# Glowdeck_beta_proto.net
KiCad netlist of a schematic drawn in EAGLE
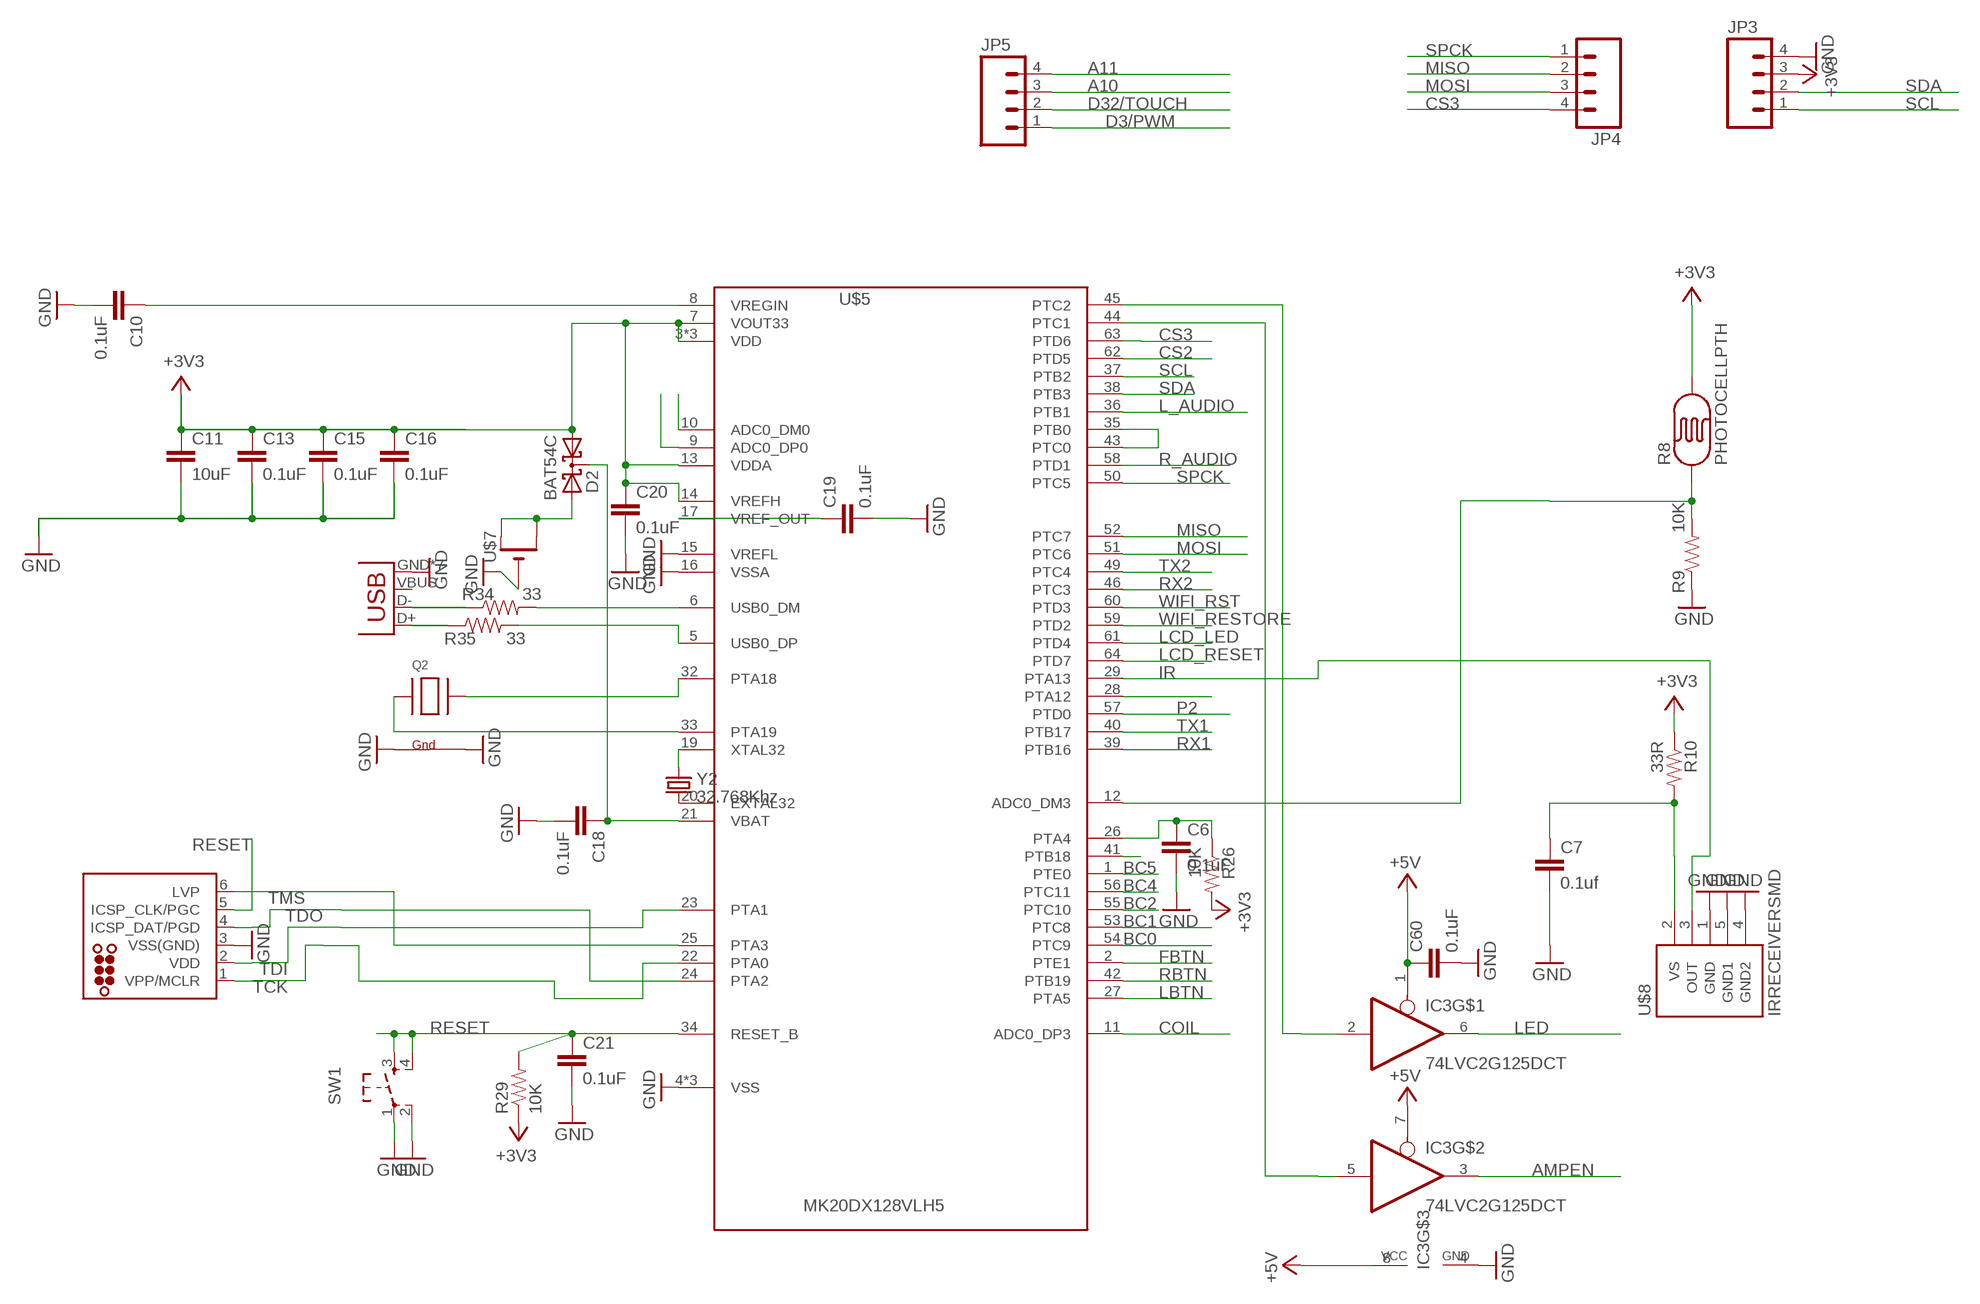
[diagram p0: schematic, sheet 1]
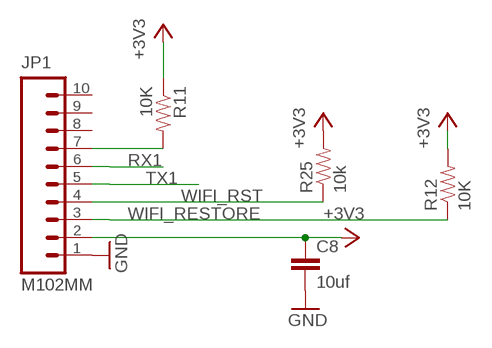
[diagram p1: schematic, sheet 2]
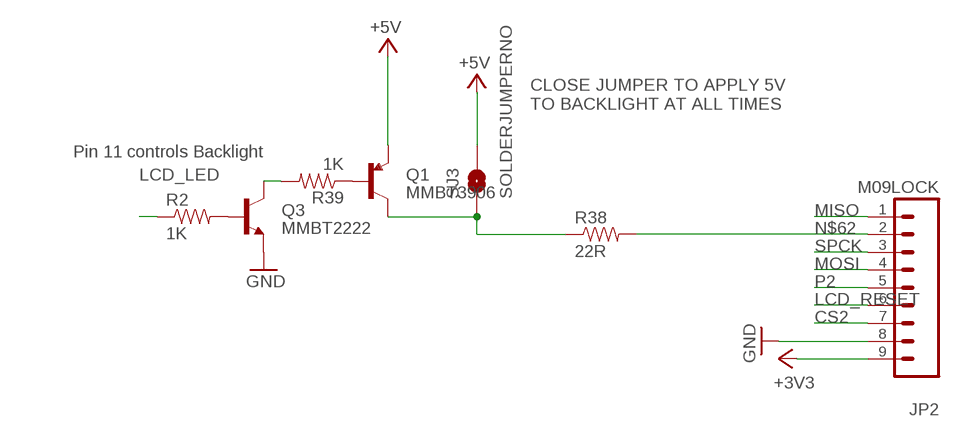
[diagram p2: schematic, sheet 3]
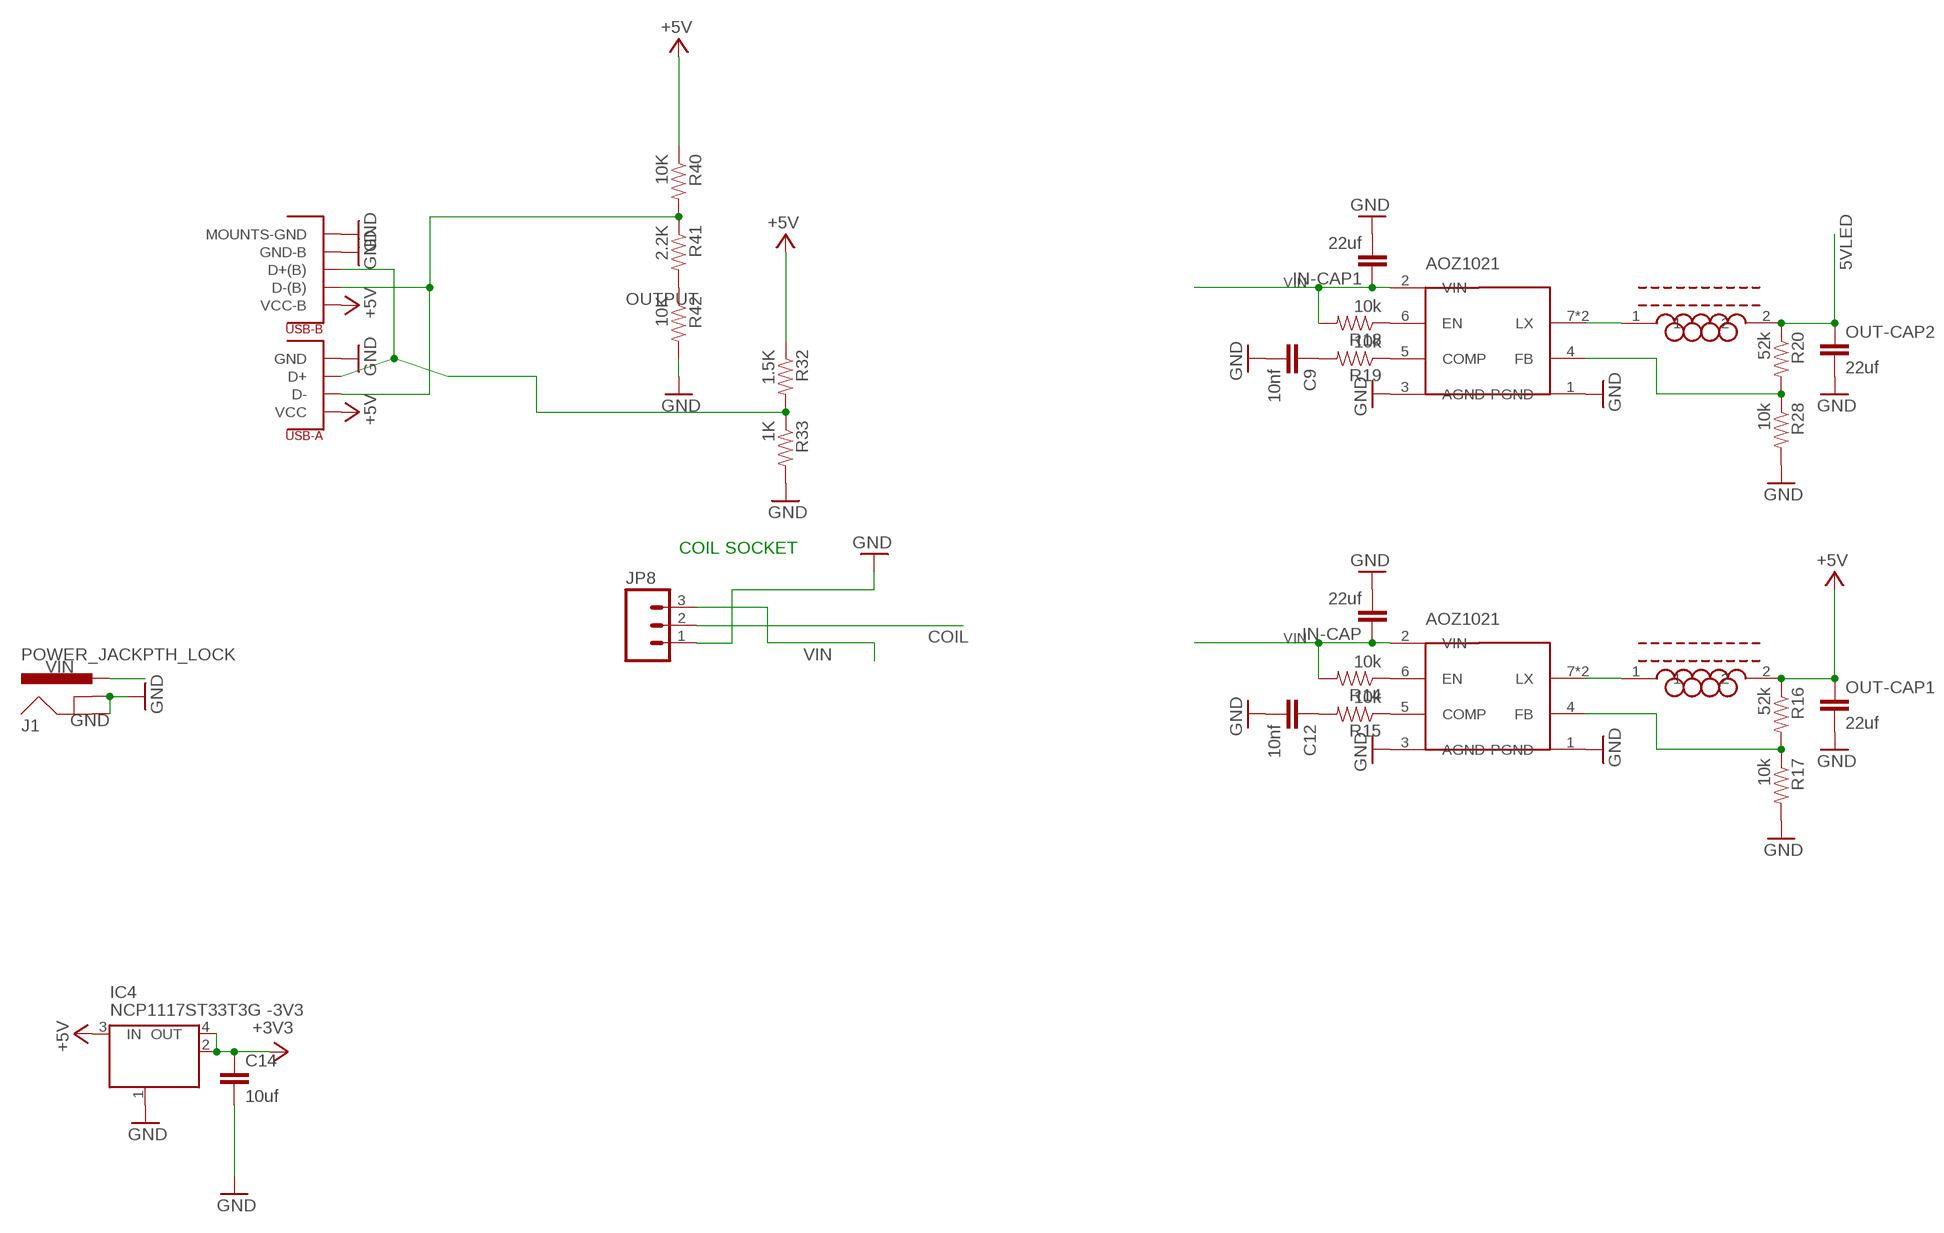
[diagram p3: schematic, sheet 4]
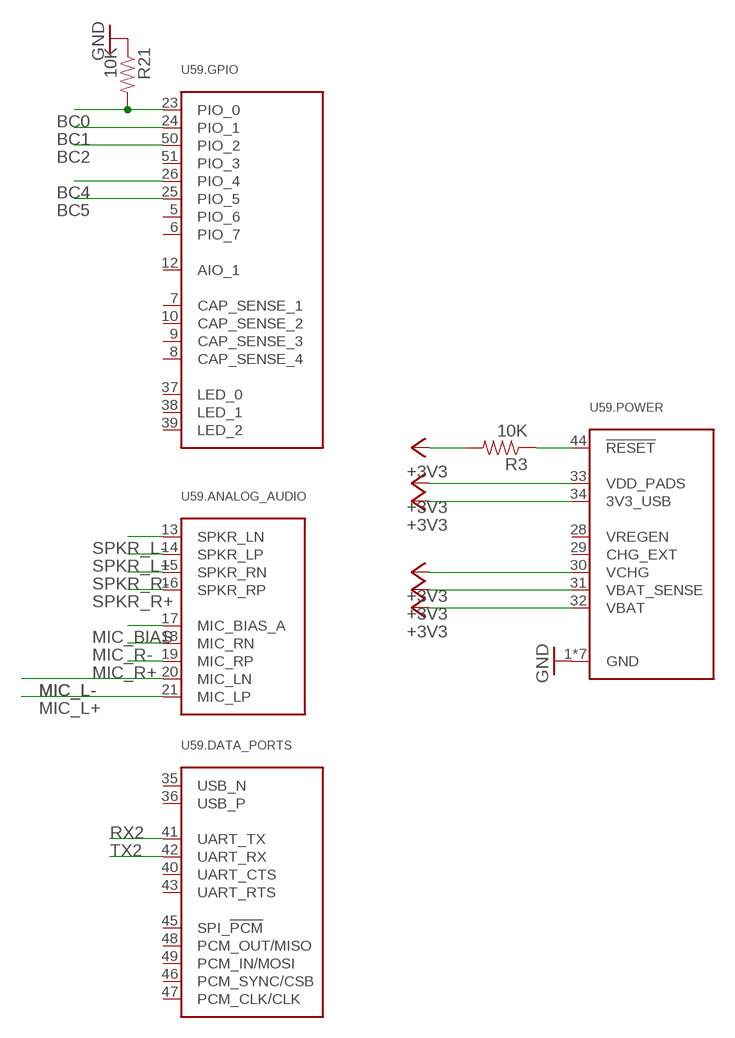
[diagram p4: schematic, sheet 5]
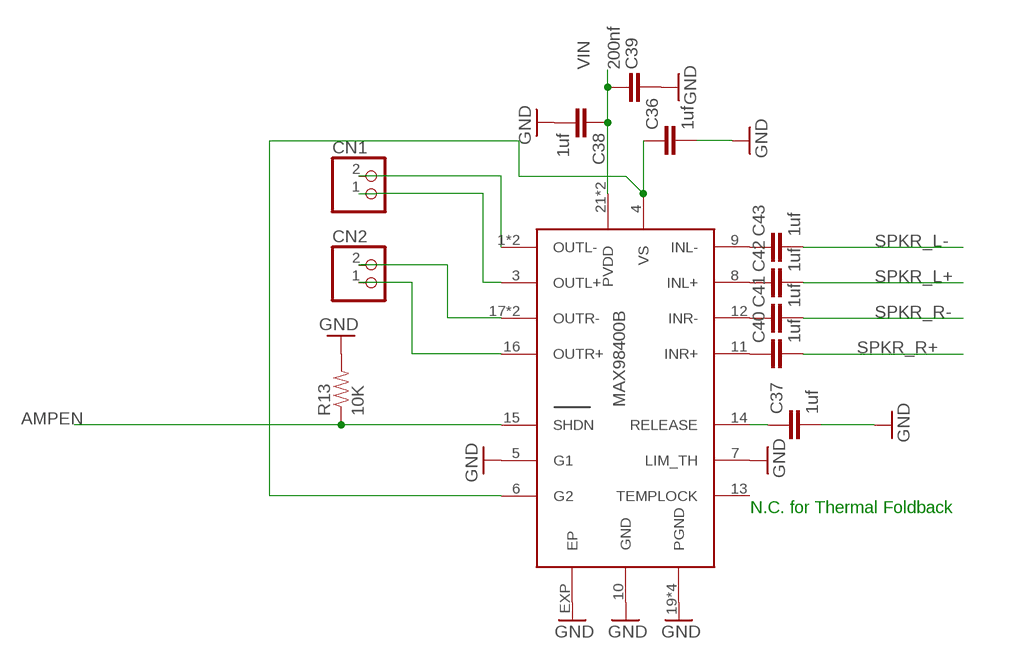
[diagram p5: schematic, sheet 6]
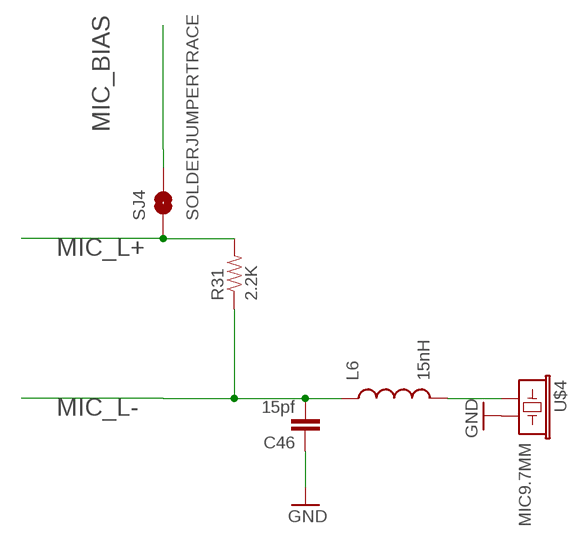
[diagram p6: schematic, sheet 7]
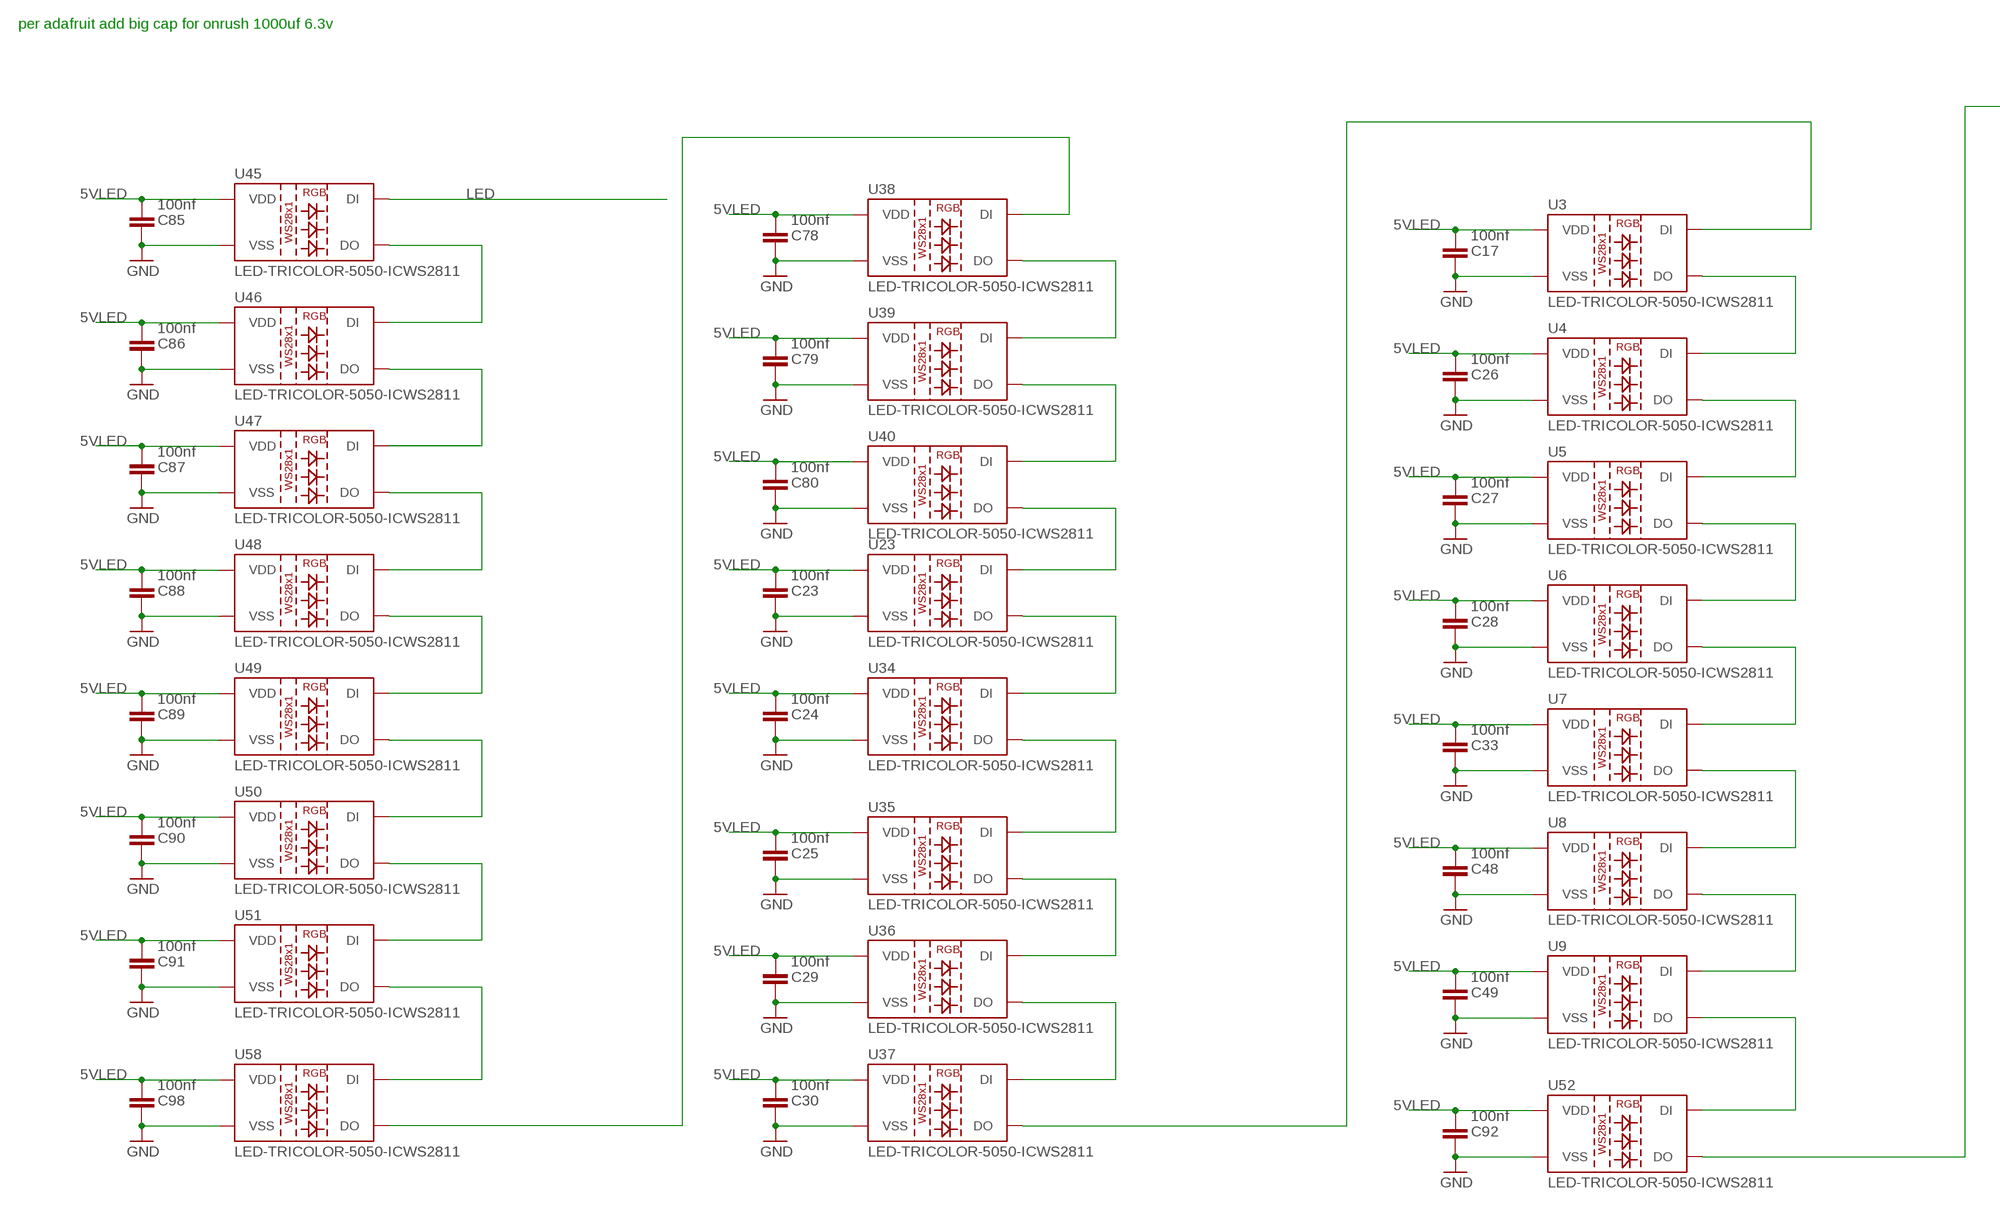
[diagram p7: schematic, sheet 8, part 1 of 2]
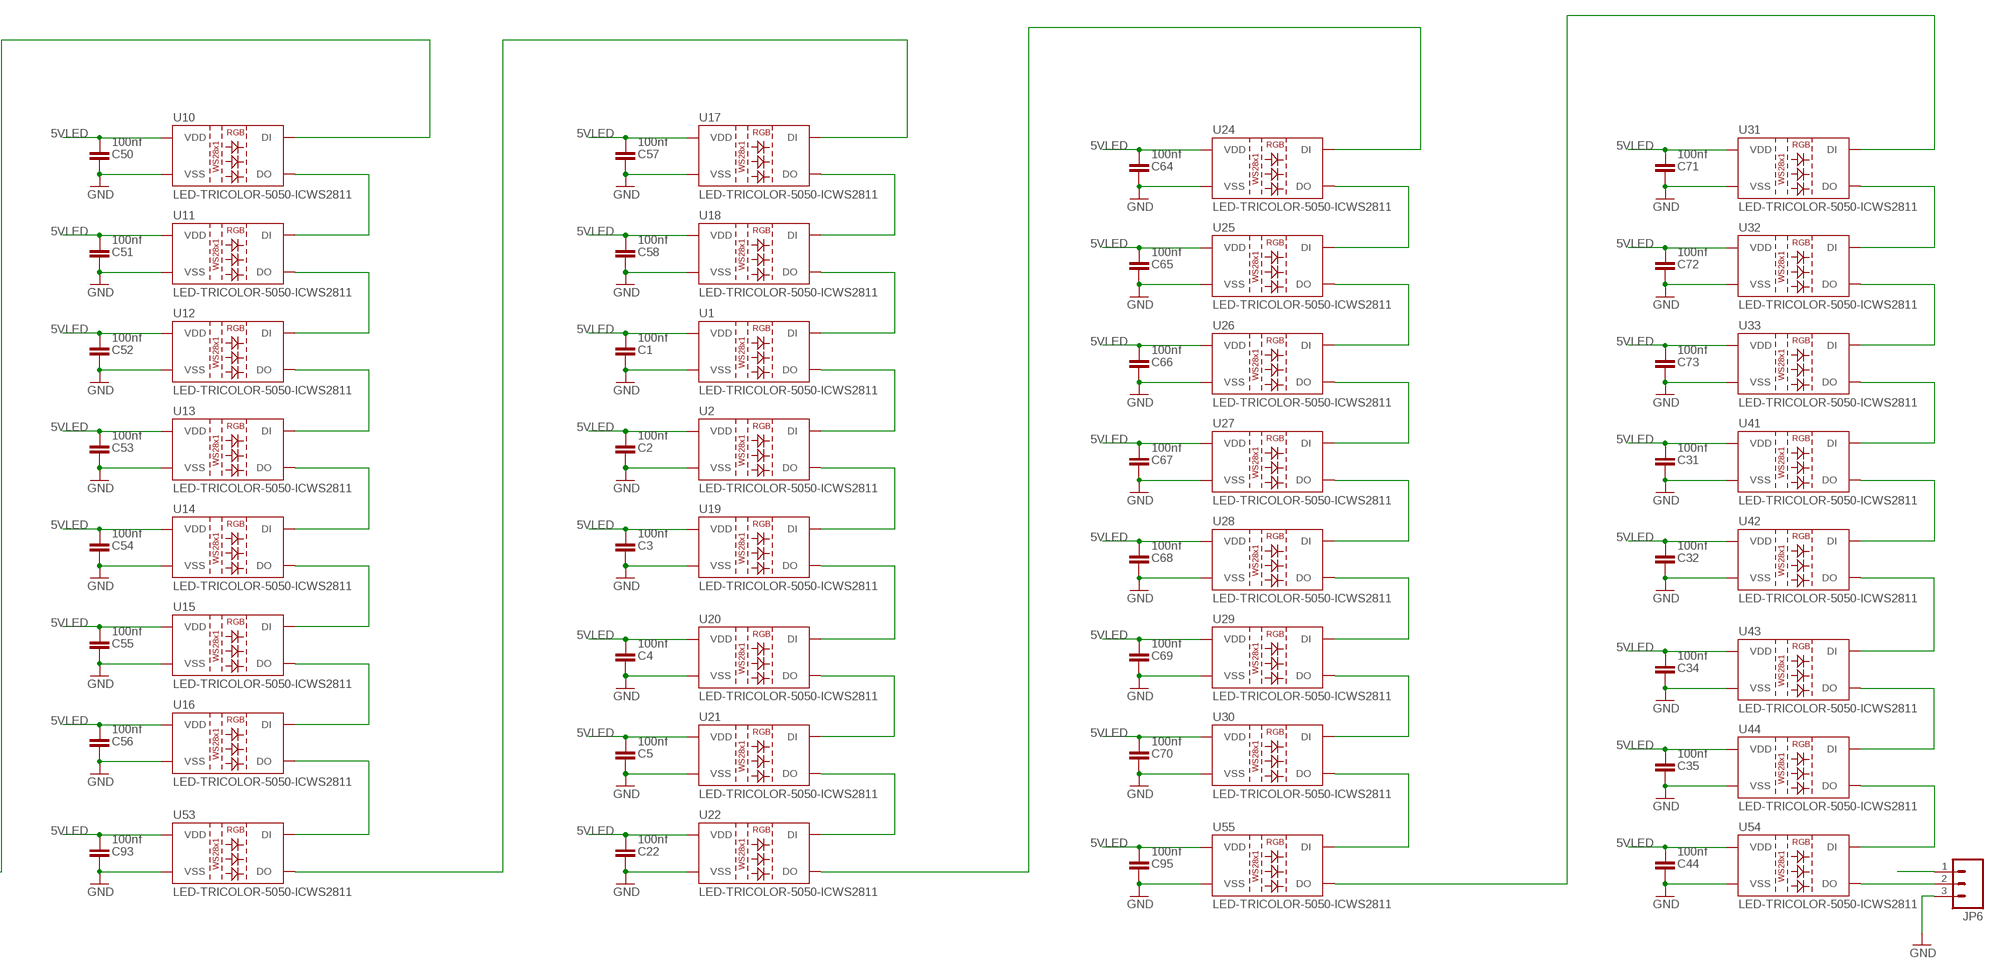
[diagram p8: schematic, sheet 8, part 2 of 2]
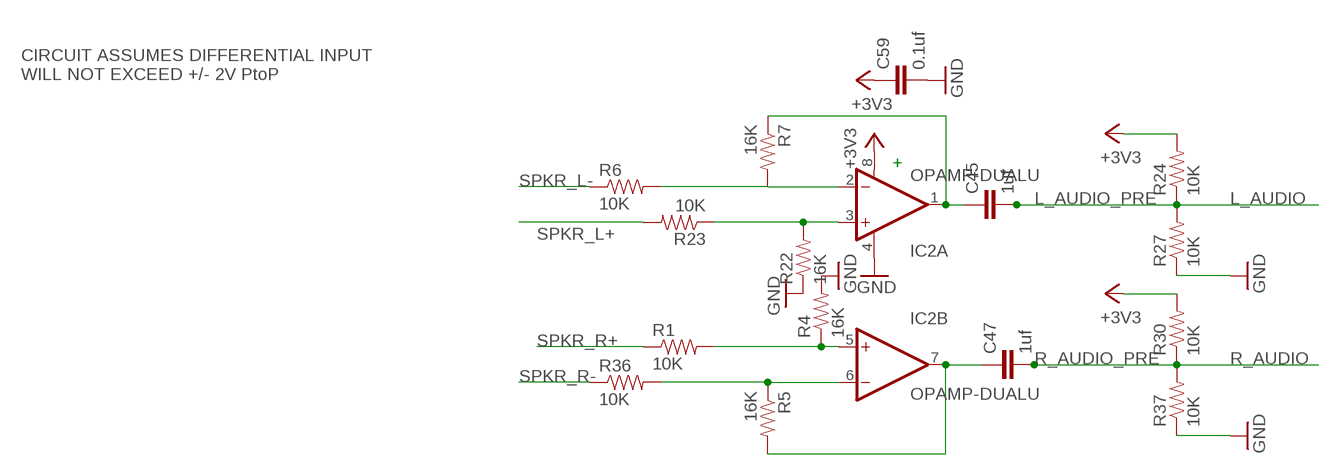
[diagram p9: schematic, sheet 9]
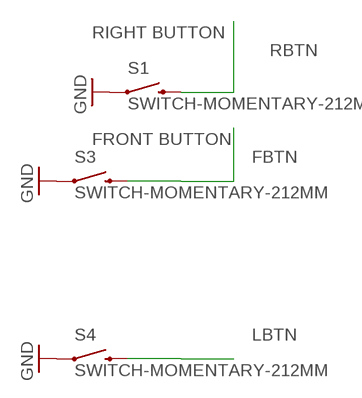
[diagram p10: schematic, sheet 10]
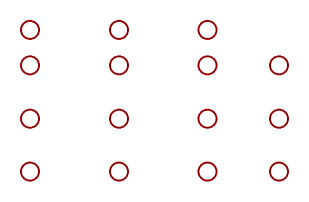
[diagram p11: schematic, sheet 11]

(export (version "E")
  (design (tool "Eeschema 10.0.6"))
  (components
    (comp (ref "C8")
      (value "10uf")
      (footprint "eagle-import:0805")
      (libsource (lib "eagle-import") (part "CAP0805"))
    )
    (comp (ref "JP1")
      (value "M102MM")
      (footprint "eagle-import:1X10-2MM")
      (libsource (lib "eagle-import") (part "M102MM"))
    )
    (comp (ref "R11")
      (value "10K")
      (footprint "eagle-import:0603-RES")
      (libsource (lib "eagle-import") (part "RESISTOR0603-RES"))
    )
    (comp (ref "R12")
      (value "10K")
      (footprint "eagle-import:0603-RES")
      (libsource (lib "eagle-import") (part "RESISTOR0603-RES"))
    )
    (comp (ref "R25")
      (value "10k")
      (footprint "eagle-import:0603-RES")
      (libsource (lib "eagle-import") (part "RESISTOR0603-RES"))
    )
    (comp (ref "C36")
      (value "1uf")
      (footprint "eagle-import:0805")
      (libsource (lib "eagle-import") (part "CAP0805"))
    )
    (comp (ref "C37")
      (value "1uf")
      (footprint "eagle-import:0805")
      (libsource (lib "eagle-import") (part "CAP0805"))
    )
    (comp (ref "C38")
      (value "1uf")
      (footprint "eagle-import:0805")
      (libsource (lib "eagle-import") (part "CAP0805"))
    )
    (comp (ref "C39")
      (value "200nf")
      (footprint "eagle-import:0603-CAP")
      (libsource (lib "eagle-import") (part "CAP0603-CAP"))
    )
    (comp (ref "C40")
      (value "1uf")
      (footprint "eagle-import:0805")
      (libsource (lib "eagle-import") (part "CAP0805"))
    )
    (comp (ref "C41")
      (value "1uf")
      (footprint "eagle-import:0805")
      (libsource (lib "eagle-import") (part "CAP0805"))
    )
    (comp (ref "C42")
      (value "1uf")
      (footprint "eagle-import:0805")
      (libsource (lib "eagle-import") (part "CAP0805"))
    )
    (comp (ref "C43")
      (value "1uf")
      (footprint "eagle-import:0805")
      (libsource (lib "eagle-import") (part "CAP0805"))
    )
    (comp (ref "CN1")
      (value "JST_2PIN-THM")
      (footprint "eagle-import:JST-PH-2-THM")
      (libsource (lib "eagle-import") (part "JST_2PIN-THM"))
    )
    (comp (ref "CN2")
      (value "JST_2PIN-THM")
      (footprint "eagle-import:JST-PH-2-THM")
      (libsource (lib "eagle-import") (part "JST_2PIN-THM"))
    )
    (comp (ref "R13")
      (value "10K")
      (footprint "eagle-import:0603-RES")
      (libsource (lib "eagle-import") (part "RESISTOR0603-RES"))
    )
    (comp (ref "U$3")
      (value "MAX98400B")
      (footprint "eagle-import:TQFN24-EP")
      (libsource (lib "eagle-import") (part "MAX98400B"))
    )
    (comp (ref "JP2")
      (value "M09LOCK")
      (footprint "eagle-import:1X09_LOCK")
      (libsource (lib "eagle-import") (part "M09LOCK"))
    )
    (comp (ref "Q1")
      (value "MMBT3906")
      (footprint "eagle-import:SOT23-3")
      (libsource (lib "eagle-import") (part "TRANSISTOR_PNPSMD"))
    )
    (comp (ref "Q3")
      (value "MMBT2222")
      (footprint "eagle-import:SOT23-3")
      (libsource (lib "eagle-import") (part "TRANSISTOR_NPNSOT23-3"))
    )
    (comp (ref "R2")
      (value "1K")
      (footprint "eagle-import:0603-RES")
      (libsource (lib "eagle-import") (part "SparkFun-Passives_RESISTOR0603-RES"))
    )
    (comp (ref "R38")
      (value "22R")
      (footprint "eagle-import:1206")
      (libsource (lib "eagle-import") (part "SparkFun-Resistors_RESISTOR1206"))
    )
    (comp (ref "R39")
      (value "1K")
      (footprint "eagle-import:0603-RES")
      (libsource (lib "eagle-import") (part "SparkFun-Passives_RESISTOR0603-RES"))
    )
    (comp (ref "SJ3")
      (value "SOLDERJUMPERNO")
      (footprint "eagle-import:SJ_2S-NO")
      (libsource (lib "eagle-import") (part "SOLDERJUMPERNO"))
    )
    (comp (ref "C6")
      (value "0.1uF")
      (footprint "eagle-import:0603-CAP")
      (libsource (lib "eagle-import") (part "SparkFun-Passives_CAP0603-CAP"))
    )
    (comp (ref "C7")
      (value "0.1uf")
      (footprint "eagle-import:0603-CAP")
      (libsource (lib "eagle-import") (part "SparkFun-Passives_CAP0603-CAP"))
    )
    (comp (ref "C10")
      (value "0.1uF")
      (footprint "eagle-import:0603-CAP")
      (libsource (lib "eagle-import") (part "SparkFun-Passives_CAP0603-CAP"))
    )
    (comp (ref "C11")
      (value "10uF")
      (footprint "eagle-import:0805")
      (libsource (lib "eagle-import") (part "SparkFun-Passives_CAP0805"))
    )
    (comp (ref "C13")
      (value "0.1uF")
      (footprint "eagle-import:0603-CAP")
      (libsource (lib "eagle-import") (part "SparkFun-Passives_CAP0603-CAP"))
    )
    (comp (ref "C15")
      (value "0.1uF")
      (footprint "eagle-import:0603-CAP")
      (libsource (lib "eagle-import") (part "SparkFun-Passives_CAP0603-CAP"))
    )
    (comp (ref "C16")
      (value "0.1uF")
      (footprint "eagle-import:0603-CAP")
      (libsource (lib "eagle-import") (part "SparkFun-Passives_CAP0603-CAP"))
    )
    (comp (ref "C18")
      (value "0.1uF")
      (footprint "eagle-import:0603-CAP")
      (libsource (lib "eagle-import") (part "SparkFun-Passives_CAP0603-CAP"))
    )
    (comp (ref "C19")
      (value "0.1uF")
      (footprint "eagle-import:0603-CAP")
      (libsource (lib "eagle-import") (part "SparkFun-Passives_CAP0603-CAP"))
    )
    (comp (ref "C20")
      (value "0.1uF")
      (footprint "eagle-import:0603-CAP")
      (libsource (lib "eagle-import") (part "SparkFun-Passives_CAP0603-CAP"))
    )
    (comp (ref "C21")
      (value "0.1uF")
      (footprint "eagle-import:0603-CAP")
      (libsource (lib "eagle-import") (part "SparkFun-Passives_CAP0603-CAP"))
    )
    (comp (ref "C60")
      (value "0.1uF")
      (footprint "eagle-import:0603-CAP")
      (libsource (lib "eagle-import") (part "SparkFun-Passives_CAP0603-CAP"))
    )
    (comp (ref "D2")
      (value "BAT54C")
      (footprint "eagle-import:SOT23")
      (libsource (lib "eagle-import") (part "BAT54C"))
    )
    (comp (ref "IC3")
      (value "74LVC2G125DCT")
      (footprint "eagle-import:SSOP08")
      (libsource (lib "eagle-import") (part "742G125DCTLVC"))
    )
    (comp (ref "J2")
      (value "TC2030-MCP-NL")
      (footprint "eagle-import:TC2030-MCP-NL")
      (libsource (lib "eagle-import") (part "TC2030-MCP-NL"))
    )
    (comp (ref "JP3")
      (value "M04LOCK")
      (footprint "eagle-import:1X04_LOCK")
      (libsource (lib "eagle-import") (part "M04LOCK"))
    )
    (comp (ref "JP4")
      (value "M04LOCK")
      (footprint "eagle-import:1X04_LOCK")
      (libsource (lib "eagle-import") (part "M04LOCK"))
    )
    (comp (ref "JP5")
      (value "M04LOCK")
      (footprint "eagle-import:1X04_LOCK")
      (libsource (lib "eagle-import") (part "M04LOCK"))
    )
    (comp (ref "Q2")
      (value "XTAL-4-3225")
      (footprint "eagle-import:NX3225")
      (libsource (lib "eagle-import") (part "XTAL-4-3225"))
    )
    (comp (ref "R8")
      (value "PHOTOCELLPTH")
      (footprint "eagle-import:PHOTOCELL")
      (libsource (lib "eagle-import") (part "PHOTOCELLPTH"))
    )
    (comp (ref "R9")
      (value "10K")
      (footprint "eagle-import:0603-RES")
      (libsource (lib "eagle-import") (part "SparkFun-Resistors_RESISTOR0603-RES"))
    )
    (comp (ref "R10")
      (value "33R")
      (footprint "eagle-import:0603-RES")
      (libsource (lib "eagle-import") (part "SparkFun-Resistors_RESISTOR0603-RES"))
    )
    (comp (ref "R26")
      (value "10K")
      (footprint "eagle-import:0603-RES")
      (libsource (lib "eagle-import") (part "SparkFun-Resistors_RESISTOR0603-RES"))
    )
    (comp (ref "R29")
      (value "10K")
      (footprint "eagle-import:0603-RES")
      (libsource (lib "eagle-import") (part "SparkFun-Resistors_RESISTOR0603-RES"))
    )
    (comp (ref "R34")
      (value "33")
      (footprint "eagle-import:0603-RES")
      (libsource (lib "eagle-import") (part "SparkFun-Resistors_RESISTOR0603-RES"))
    )
    (comp (ref "R35")
      (value "33")
      (footprint "eagle-import:0603-RES")
      (libsource (lib "eagle-import") (part "SparkFun-Resistors_RESISTOR0603-RES"))
    )
    (comp (ref "SW1")
      (value "SW_TACT_4P")
      (footprint "eagle-import:SW_TACT_SMALL")
      (libsource (lib "eagle-import") (part "SW_TACT_4P"))
    )
    (comp (ref "U$5")
      (value "MK20DX128VLH5")
      (footprint "eagle-import:MK20DX128VLH5")
      (libsource (lib "eagle-import") (part "MK20DX128VLH5"))
    )
    (comp (ref "U$7")
      (value "CR1220THM")
      (footprint "eagle-import:CR1220-THM")
      (libsource (lib "eagle-import") (part "CR1220THM"))
    )
    (comp (ref "U$8")
      (value "IRRECEIVERSMD")
      (footprint "eagle-import:TSOP8523")
      (libsource (lib "eagle-import") (part "IRRECEIVERSMD"))
    )
    (comp (ref "X3")
      (value "USB-MICROB")
      (footprint "eagle-import:USB-MICROB")
      (libsource (lib "eagle-import") (part "USB-MICROB"))
    )
    (comp (ref "Y2")
      (value "32.768Khz")
      (footprint "eagle-import:RESONATOR_EPSON_FC_145")
      (libsource (lib "eagle-import") (part "RESONATOR_EPSON_FC_145"))
    )
    (comp (ref "AOZ1015AI")
      (value "AOZ1021")
      (footprint "eagle-import:SO-08")
      (libsource (lib "eagle-import") (part "AOZ1021"))
    )
    (comp (ref "AOZ1015AI1")
      (value "AOZ1021")
      (footprint "eagle-import:SO-08")
      (libsource (lib "eagle-import") (part "AOZ1021"))
    )
    (comp (ref "C9")
      (value "10nf")
      (footprint "eagle-import:0603-CAP")
      (libsource (lib "eagle-import") (part "CAP0603-CAP"))
    )
    (comp (ref "C12")
      (value "10nf")
      (footprint "eagle-import:0603-CAP")
      (libsource (lib "eagle-import") (part "CAP0603-CAP"))
    )
    (comp (ref "C14")
      (value "10uf")
      (footprint "eagle-import:0805")
      (libsource (lib "eagle-import") (part "CAP0805"))
    )
    (comp (ref "IC4")
      (value "NCP1117ST33T3G -3V3")
      (footprint "eagle-import:SOT223")
      (libsource (lib "eagle-import") (part "MC33269ST-3.3T3"))
    )
    (comp (ref "IN-CAP")
      (value "22uf")
      (footprint "eagle-import:1210")
      (libsource (lib "eagle-import") (part "CAP1210"))
    )
    (comp (ref "IN-CAP1")
      (value "22uf")
      (footprint "eagle-import:1210")
      (libsource (lib "eagle-import") (part "CAP1210"))
    )
    (comp (ref "J1")
      (value "POWER_JACKPTH_LOCK")
      (footprint "eagle-import:POWER_JACK_PTH_LOCK")
      (libsource (lib "eagle-import") (part "POWER_JACKPTH_LOCK"))
    )
    (comp (ref "JP8")
      (value "M03JST-PTH")
      (footprint "eagle-import:JST-3-PTH")
      (libsource (lib "eagle-import") (part "M03JST-PTH"))
    )
    (comp (ref "OUT-CAP1")
      (value "22uf")
      (footprint "eagle-import:1210")
      (libsource (lib "eagle-import") (part "CAP1210"))
    )
    (comp (ref "OUT-CAP2")
      (value "22uf")
      (footprint "eagle-import:1210")
      (libsource (lib "eagle-import") (part "CAP1210"))
    )
    (comp (ref "R14")
      (value "10k")
      (footprint "eagle-import:0603-RES")
      (libsource (lib "eagle-import") (part "RESISTOR0603-RES"))
    )
    (comp (ref "R15")
      (value "10k")
      (footprint "eagle-import:0603-RES")
      (libsource (lib "eagle-import") (part "RESISTOR0603-RES"))
    )
    (comp (ref "R16")
      (value "52k")
      (footprint "eagle-import:0603-RES")
      (libsource (lib "eagle-import") (part "RESISTOR0603-RES"))
    )
    (comp (ref "R17")
      (value "10k")
      (footprint "eagle-import:0603-RES")
      (libsource (lib "eagle-import") (part "RESISTOR0603-RES"))
    )
    (comp (ref "R18")
      (value "10k")
      (footprint "eagle-import:0603-RES")
      (libsource (lib "eagle-import") (part "RESISTOR0603-RES"))
    )
    (comp (ref "R19")
      (value "10k")
      (footprint "eagle-import:0603-RES")
      (libsource (lib "eagle-import") (part "RESISTOR0603-RES"))
    )
    (comp (ref "R20")
      (value "52k")
      (footprint "eagle-import:0603-RES")
      (libsource (lib "eagle-import") (part "RESISTOR0603-RES"))
    )
    (comp (ref "R28")
      (value "10k")
      (footprint "eagle-import:0603-RES")
      (libsource (lib "eagle-import") (part "RESISTOR0603-RES"))
    )
    (comp (ref "R32")
      (value "1.5K")
      (footprint "eagle-import:0603-RES")
      (libsource (lib "eagle-import") (part "SparkFun-Passives_RESISTOR0603-RES"))
    )
    (comp (ref "R33")
      (value "1K")
      (footprint "eagle-import:0603-RES")
      (libsource (lib "eagle-import") (part "SparkFun-Passives_RESISTOR0603-RES"))
    )
    (comp (ref "R40")
      (value "10K")
      (footprint "eagle-import:0603-RES")
      (libsource (lib "eagle-import") (part "SparkFun-Passives_RESISTOR0603-RES"))
    )
    (comp (ref "R41")
      (value "2.2K")
      (footprint "eagle-import:0603-RES")
      (libsource (lib "eagle-import") (part "SparkFun-Passives_RESISTOR0603-RES"))
    )
    (comp (ref "R42")
      (value "10K")
      (footprint "eagle-import:0603-RES")
      (libsource (lib "eagle-import") (part "SparkFun-Passives_RESISTOR0603-RES"))
    )
    (comp (ref "U$1")
      (value "SRP7030F")
      (footprint "eagle-import:SRP7030")
      (libsource (lib "eagle-import") (part "SRP7030F"))
    )
    (comp (ref "U$2")
      (value "SRP7030F")
      (footprint "eagle-import:SRP7030")
      (libsource (lib "eagle-import") (part "SRP7030F"))
    )
    (comp (ref "U$6")
      (value "DUAL-PORT-USB-REC")
      (footprint "eagle-import:DUAL-PORT-USB")
      (libsource (lib "eagle-import") (part "DUAL-PORT-USB-REC"))
    )
    (comp (ref "R3")
      (value "10K")
      (footprint "eagle-import:0603-RES")
      (libsource (lib "eagle-import") (part "RESISTOR0603-RES"))
    )
    (comp (ref "R21")
      (value "10K")
      (footprint "eagle-import:0603-RES")
      (libsource (lib "eagle-import") (part "RESISTOR0603-RES"))
    )
    (comp (ref "U59")
      (value "BC127EXTRA_PASTE")
      (footprint "eagle-import:BC127_XTRA_PASTE")
      (libsource (lib "eagle-import") (part "BC127EXTRA_PASTE"))
    )
    (comp (ref "C46")
      (value "15pf")
      (footprint "eagle-import:0805")
      (libsource (lib "eagle-import") (part "CAP0805"))
    )
    (comp (ref "L6")
      (value "15nH")
      (footprint "eagle-import:0603")
      (libsource (lib "eagle-import") (part "INDUCTOR0603"))
    )
    (comp (ref "R31")
      (value "2.2K")
      (footprint "eagle-import:0603-RES")
      (libsource (lib "eagle-import") (part "RESISTOR0603-RES"))
    )
    (comp (ref "SJ4")
      (value "SOLDERJUMPERTRACE")
      (footprint "eagle-import:SJ_2S-TRACE")
      (libsource (lib "eagle-import") (part "SOLDERJUMPERTRACE"))
    )
    (comp (ref "U$4")
      (value "MIC9.7MM")
      (footprint "eagle-import:MIC-9.7MM")
      (libsource (lib "eagle-import") (part "MIC9.7MM"))
    )
    (comp (ref "STANDOFF1")
      (value "STAND-OFF")
      (footprint "eagle-import:STAND-OFF")
      (libsource (lib "eagle-import") (part "STAND-OFF"))
    )
    (comp (ref "STANDOFF2")
      (value "STAND-OFF")
      (footprint "eagle-import:STAND-OFF")
      (libsource (lib "eagle-import") (part "STAND-OFF"))
    )
    (comp (ref "STANDOFF3")
      (value "STAND-OFF")
      (footprint "eagle-import:STAND-OFF")
      (libsource (lib "eagle-import") (part "STAND-OFF"))
    )
    (comp (ref "STANDOFF4")
      (value "STAND-OFF")
      (footprint "eagle-import:STAND-OFF")
      (libsource (lib "eagle-import") (part "STAND-OFF"))
    )
    (comp (ref "STANDOFF5")
      (value "STAND-OFF")
      (footprint "eagle-import:STAND-OFF")
      (libsource (lib "eagle-import") (part "STAND-OFF"))
    )
    (comp (ref "STANDOFF6")
      (value "STAND-OFF")
      (footprint "eagle-import:STAND-OFF")
      (libsource (lib "eagle-import") (part "STAND-OFF"))
    )
    (comp (ref "STANDOFF7")
      (value "STAND-OFF")
      (footprint "eagle-import:STAND-OFF")
      (libsource (lib "eagle-import") (part "STAND-OFF"))
    )
    (comp (ref "STANDOFF8")
      (value "STAND-OFF")
      (footprint "eagle-import:STAND-OFF")
      (libsource (lib "eagle-import") (part "STAND-OFF"))
    )
    (comp (ref "STANDOFF9")
      (value "STAND-OFF")
      (footprint "eagle-import:STAND-OFF")
      (libsource (lib "eagle-import") (part "STAND-OFF"))
    )
    (comp (ref "STANDOFF10")
      (value "STAND-OFF")
      (footprint "eagle-import:STAND-OFF")
      (libsource (lib "eagle-import") (part "STAND-OFF"))
    )
    (comp (ref "STANDOFF11")
      (value "STAND-OFF")
      (footprint "eagle-import:STAND-OFF")
      (libsource (lib "eagle-import") (part "STAND-OFF"))
    )
    (comp (ref "STANDOFF12")
      (value "STAND-OFF")
      (footprint "eagle-import:STAND-OFF")
      (libsource (lib "eagle-import") (part "STAND-OFF"))
    )
    (comp (ref "STANDOFF13")
      (value "STAND-OFF")
      (footprint "eagle-import:STAND-OFF")
      (libsource (lib "eagle-import") (part "STAND-OFF"))
    )
    (comp (ref "STANDOFF14")
      (value "STAND-OFF")
      (footprint "eagle-import:STAND-OFF")
      (libsource (lib "eagle-import") (part "STAND-OFF"))
    )
    (comp (ref "STANDOFF15")
      (value "STAND-OFF")
      (footprint "eagle-import:STAND-OFF")
      (libsource (lib "eagle-import") (part "STAND-OFF"))
    )
    (comp (ref "S1")
      (value "SWITCH-MOMENTARY-212MM")
      (footprint "eagle-import:TACTILE-PTH-12MM")
      (libsource (lib "eagle-import") (part "SWITCH-MOMENTARY-212MM"))
    )
    (comp (ref "S3")
      (value "SWITCH-MOMENTARY-212MM")
      (footprint "eagle-import:TACTILE-PTH-12MM")
      (libsource (lib "eagle-import") (part "SWITCH-MOMENTARY-212MM"))
    )
    (comp (ref "S4")
      (value "SWITCH-MOMENTARY-212MM")
      (footprint "eagle-import:TACTILE-PTH-12MM")
      (libsource (lib "eagle-import") (part "SWITCH-MOMENTARY-212MM"))
    )
    (comp (ref "C45")
      (value "1uf")
      (footprint "eagle-import:0805")
      (libsource (lib "eagle-import") (part "SparkFun-Passives_CAP0805"))
    )
    (comp (ref "C47")
      (value "1uf")
      (footprint "eagle-import:0805")
      (libsource (lib "eagle-import") (part "SparkFun-Passives_CAP0805"))
    )
    (comp (ref "C59")
      (value "0.1uf")
      (footprint "eagle-import:0603-CAP")
      (libsource (lib "eagle-import") (part "SparkFun-Passives_CAP0603-CAP"))
    )
    (comp (ref "IC2")
      (value "OPAMP-DUALU")
      (footprint "eagle-import:SO08")
      (libsource (lib "eagle-import") (part "OPAMP-DUALU"))
    )
    (comp (ref "R1")
      (value "10K")
      (footprint "eagle-import:0603-RES")
      (libsource (lib "eagle-import") (part "RESISTOR0603-RES"))
    )
    (comp (ref "R4")
      (value "16K")
      (footprint "eagle-import:0603-RES")
      (libsource (lib "eagle-import") (part "RESISTOR0603-RES"))
    )
    (comp (ref "R5")
      (value "16K")
      (footprint "eagle-import:0603-RES")
      (libsource (lib "eagle-import") (part "RESISTOR0603-RES"))
    )
    (comp (ref "R6")
      (value "10K")
      (footprint "eagle-import:0603-RES")
      (libsource (lib "eagle-import") (part "RESISTOR0603-RES"))
    )
    (comp (ref "R7")
      (value "16K")
      (footprint "eagle-import:0603-RES")
      (libsource (lib "eagle-import") (part "RESISTOR0603-RES"))
    )
    (comp (ref "R22")
      (value "16K")
      (footprint "eagle-import:0603-RES")
      (libsource (lib "eagle-import") (part "RESISTOR0603-RES"))
    )
    (comp (ref "R23")
      (value "10K")
      (footprint "eagle-import:0603-RES")
      (libsource (lib "eagle-import") (part "RESISTOR0603-RES"))
    )
    (comp (ref "R24")
      (value "10K")
      (footprint "eagle-import:0603-RES")
      (libsource (lib "eagle-import") (part "RESISTOR0603-RES"))
    )
    (comp (ref "R27")
      (value "10K")
      (footprint "eagle-import:0603-RES")
      (libsource (lib "eagle-import") (part "RESISTOR0603-RES"))
    )
    (comp (ref "R30")
      (value "10K")
      (footprint "eagle-import:0603-RES")
      (libsource (lib "eagle-import") (part "RESISTOR0603-RES"))
    )
    (comp (ref "R36")
      (value "10K")
      (footprint "eagle-import:0603-RES")
      (libsource (lib "eagle-import") (part "RESISTOR0603-RES"))
    )
    (comp (ref "R37")
      (value "10K")
      (footprint "eagle-import:0603-RES")
      (libsource (lib "eagle-import") (part "RESISTOR0603-RES"))
    )
    (comp (ref "C1")
      (value "100nf")
      (footprint "eagle-import:0603-CAP")
      (libsource (lib "eagle-import") (part "CAP0603-CAP"))
    )
    (comp (ref "C2")
      (value "100nf")
      (footprint "eagle-import:0603-CAP")
      (libsource (lib "eagle-import") (part "CAP0603-CAP"))
    )
    (comp (ref "C3")
      (value "100nf")
      (footprint "eagle-import:0603-CAP")
      (libsource (lib "eagle-import") (part "CAP0603-CAP"))
    )
    (comp (ref "C4")
      (value "100nf")
      (footprint "eagle-import:0603-CAP")
      (libsource (lib "eagle-import") (part "CAP0603-CAP"))
    )
    (comp (ref "C5")
      (value "100nf")
      (footprint "eagle-import:0603-CAP")
      (libsource (lib "eagle-import") (part "CAP0603-CAP"))
    )
    (comp (ref "C17")
      (value "100nf")
      (footprint "eagle-import:0603-CAP")
      (libsource (lib "eagle-import") (part "CAP0603-CAP"))
    )
    (comp (ref "C22")
      (value "100nf")
      (footprint "eagle-import:0603-CAP")
      (libsource (lib "eagle-import") (part "CAP0603-CAP"))
    )
    (comp (ref "C23")
      (value "100nf")
      (footprint "eagle-import:0603-CAP")
      (libsource (lib "eagle-import") (part "CAP0603-CAP"))
    )
    (comp (ref "C24")
      (value "100nf")
      (footprint "eagle-import:0603-CAP")
      (libsource (lib "eagle-import") (part "CAP0603-CAP"))
    )
    (comp (ref "C25")
      (value "100nf")
      (footprint "eagle-import:0603-CAP")
      (libsource (lib "eagle-import") (part "CAP0603-CAP"))
    )
    (comp (ref "C26")
      (value "100nf")
      (footprint "eagle-import:0603-CAP")
      (libsource (lib "eagle-import") (part "CAP0603-CAP"))
    )
    (comp (ref "C27")
      (value "100nf")
      (footprint "eagle-import:0603-CAP")
      (libsource (lib "eagle-import") (part "CAP0603-CAP"))
    )
    (comp (ref "C28")
      (value "100nf")
      (footprint "eagle-import:0603-CAP")
      (libsource (lib "eagle-import") (part "CAP0603-CAP"))
    )
    (comp (ref "C29")
      (value "100nf")
      (footprint "eagle-import:0603-CAP")
      (libsource (lib "eagle-import") (part "CAP0603-CAP"))
    )
    (comp (ref "C30")
      (value "100nf")
      (footprint "eagle-import:0603-CAP")
      (libsource (lib "eagle-import") (part "CAP0603-CAP"))
    )
    (comp (ref "C31")
      (value "100nf")
      (footprint "eagle-import:0603-CAP")
      (libsource (lib "eagle-import") (part "CAP0603-CAP"))
    )
    (comp (ref "C32")
      (value "100nf")
      (footprint "eagle-import:0603-CAP")
      (libsource (lib "eagle-import") (part "CAP0603-CAP"))
    )
    (comp (ref "C33")
      (value "100nf")
      (footprint "eagle-import:0603-CAP")
      (libsource (lib "eagle-import") (part "CAP0603-CAP"))
    )
    (comp (ref "C34")
      (value "100nf")
      (footprint "eagle-import:0603-CAP")
      (libsource (lib "eagle-import") (part "CAP0603-CAP"))
    )
    (comp (ref "C35")
      (value "100nf")
      (footprint "eagle-import:0603-CAP")
      (libsource (lib "eagle-import") (part "CAP0603-CAP"))
    )
    (comp (ref "C44")
      (value "100nf")
      (footprint "eagle-import:0603-CAP")
      (libsource (lib "eagle-import") (part "CAP0603-CAP"))
    )
    (comp (ref "C48")
      (value "100nf")
      (footprint "eagle-import:0603-CAP")
      (libsource (lib "eagle-import") (part "CAP0603-CAP"))
    )
    (comp (ref "C49")
      (value "100nf")
      (footprint "eagle-import:0603-CAP")
      (libsource (lib "eagle-import") (part "CAP0603-CAP"))
    )
    (comp (ref "C50")
      (value "100nf")
      (footprint "eagle-import:0603-CAP")
      (libsource (lib "eagle-import") (part "CAP0603-CAP"))
    )
    (comp (ref "C51")
      (value "100nf")
      (footprint "eagle-import:0603-CAP")
      (libsource (lib "eagle-import") (part "CAP0603-CAP"))
    )
    (comp (ref "C52")
      (value "100nf")
      (footprint "eagle-import:0603-CAP")
      (libsource (lib "eagle-import") (part "CAP0603-CAP"))
    )
    (comp (ref "C53")
      (value "100nf")
      (footprint "eagle-import:0603-CAP")
      (libsource (lib "eagle-import") (part "CAP0603-CAP"))
    )
    (comp (ref "C54")
      (value "100nf")
      (footprint "eagle-import:0603-CAP")
      (libsource (lib "eagle-import") (part "CAP0603-CAP"))
    )
    (comp (ref "C55")
      (value "100nf")
      (footprint "eagle-import:0603-CAP")
      (libsource (lib "eagle-import") (part "CAP0603-CAP"))
    )
    (comp (ref "C56")
      (value "100nf")
      (footprint "eagle-import:0603-CAP")
      (libsource (lib "eagle-import") (part "CAP0603-CAP"))
    )
    (comp (ref "C57")
      (value "100nf")
      (footprint "eagle-import:0603-CAP")
      (libsource (lib "eagle-import") (part "CAP0603-CAP"))
    )
    (comp (ref "C58")
      (value "100nf")
      (footprint "eagle-import:0603-CAP")
      (libsource (lib "eagle-import") (part "CAP0603-CAP"))
    )
    (comp (ref "C64")
      (value "100nf")
      (footprint "eagle-import:0603-CAP")
      (libsource (lib "eagle-import") (part "CAP0603-CAP"))
    )
    (comp (ref "C65")
      (value "100nf")
      (footprint "eagle-import:0603-CAP")
      (libsource (lib "eagle-import") (part "CAP0603-CAP"))
    )
    (comp (ref "C66")
      (value "100nf")
      (footprint "eagle-import:0603-CAP")
      (libsource (lib "eagle-import") (part "CAP0603-CAP"))
    )
    (comp (ref "C67")
      (value "100nf")
      (footprint "eagle-import:0603-CAP")
      (libsource (lib "eagle-import") (part "CAP0603-CAP"))
    )
    (comp (ref "C68")
      (value "100nf")
      (footprint "eagle-import:0603-CAP")
      (libsource (lib "eagle-import") (part "CAP0603-CAP"))
    )
    (comp (ref "C69")
      (value "100nf")
      (footprint "eagle-import:0603-CAP")
      (libsource (lib "eagle-import") (part "CAP0603-CAP"))
    )
    (comp (ref "C70")
      (value "100nf")
      (footprint "eagle-import:0603-CAP")
      (libsource (lib "eagle-import") (part "CAP0603-CAP"))
    )
    (comp (ref "C71")
      (value "100nf")
      (footprint "eagle-import:0603-CAP")
      (libsource (lib "eagle-import") (part "CAP0603-CAP"))
    )
    (comp (ref "C72")
      (value "100nf")
      (footprint "eagle-import:0603-CAP")
      (libsource (lib "eagle-import") (part "CAP0603-CAP"))
    )
    (comp (ref "C73")
      (value "100nf")
      (footprint "eagle-import:0603-CAP")
      (libsource (lib "eagle-import") (part "CAP0603-CAP"))
    )
    (comp (ref "C78")
      (value "100nf")
      (footprint "eagle-import:0603-CAP")
      (libsource (lib "eagle-import") (part "CAP0603-CAP"))
    )
    (comp (ref "C79")
      (value "100nf")
      (footprint "eagle-import:0603-CAP")
      (libsource (lib "eagle-import") (part "CAP0603-CAP"))
    )
    (comp (ref "C80")
      (value "100nf")
      (footprint "eagle-import:0603-CAP")
      (libsource (lib "eagle-import") (part "CAP0603-CAP"))
    )
    (comp (ref "C85")
      (value "100nf")
      (footprint "eagle-import:0603-CAP")
      (libsource (lib "eagle-import") (part "CAP0603-CAP"))
    )
    (comp (ref "C86")
      (value "100nf")
      (footprint "eagle-import:0603-CAP")
      (libsource (lib "eagle-import") (part "CAP0603-CAP"))
    )
    (comp (ref "C87")
      (value "100nf")
      (footprint "eagle-import:0603-CAP")
      (libsource (lib "eagle-import") (part "CAP0603-CAP"))
    )
    (comp (ref "C88")
      (value "100nf")
      (footprint "eagle-import:0603-CAP")
      (libsource (lib "eagle-import") (part "CAP0603-CAP"))
    )
    (comp (ref "C89")
      (value "100nf")
      (footprint "eagle-import:0603-CAP")
      (libsource (lib "eagle-import") (part "CAP0603-CAP"))
    )
    (comp (ref "C90")
      (value "100nf")
      (footprint "eagle-import:0603-CAP")
      (libsource (lib "eagle-import") (part "CAP0603-CAP"))
    )
    (comp (ref "C91")
      (value "100nf")
      (footprint "eagle-import:0603-CAP")
      (libsource (lib "eagle-import") (part "CAP0603-CAP"))
    )
    (comp (ref "C92")
      (value "100nf")
      (footprint "eagle-import:0603-CAP")
      (libsource (lib "eagle-import") (part "CAP0603-CAP"))
    )
    (comp (ref "C93")
      (value "100nf")
      (footprint "eagle-import:0603-CAP")
      (libsource (lib "eagle-import") (part "CAP0603-CAP"))
    )
    (comp (ref "C95")
      (value "100nf")
      (footprint "eagle-import:0603-CAP")
      (libsource (lib "eagle-import") (part "CAP0603-CAP"))
    )
    (comp (ref "C98")
      (value "100nf")
      (footprint "eagle-import:0603-CAP")
      (libsource (lib "eagle-import") (part "CAP0603-CAP"))
    )
    (comp (ref "JP6")
      (value "M03LOCK")
      (footprint "eagle-import:1X03_LOCK")
      (libsource (lib "eagle-import") (part "M03LOCK"))
    )
    (comp (ref "U1")
      (value "LED-TRICOLOR-5050-ICWS2811")
      (footprint "eagle-import:LED-TRICOLOR-5050-IC")
      (libsource (lib "eagle-import") (part "LED-TRICOLOR-5050-ICWS2811"))
    )
    (comp (ref "U2")
      (value "LED-TRICOLOR-5050-ICWS2811")
      (footprint "eagle-import:LED-TRICOLOR-5050-IC")
      (libsource (lib "eagle-import") (part "LED-TRICOLOR-5050-ICWS2811"))
    )
    (comp (ref "U3")
      (value "LED-TRICOLOR-5050-ICWS2811")
      (footprint "eagle-import:LED-TRICOLOR-5050-IC")
      (libsource (lib "eagle-import") (part "LED-TRICOLOR-5050-ICWS2811"))
    )
    (comp (ref "U4")
      (value "LED-TRICOLOR-5050-ICWS2811")
      (footprint "eagle-import:LED-TRICOLOR-5050-IC")
      (libsource (lib "eagle-import") (part "LED-TRICOLOR-5050-ICWS2811"))
    )
    (comp (ref "U5")
      (value "LED-TRICOLOR-5050-ICWS2811")
      (footprint "eagle-import:LED-TRICOLOR-5050-IC")
      (libsource (lib "eagle-import") (part "LED-TRICOLOR-5050-ICWS2811"))
    )
    (comp (ref "U6")
      (value "LED-TRICOLOR-5050-ICWS2811")
      (footprint "eagle-import:LED-TRICOLOR-5050-IC")
      (libsource (lib "eagle-import") (part "LED-TRICOLOR-5050-ICWS2811"))
    )
    (comp (ref "U7")
      (value "LED-TRICOLOR-5050-ICWS2811")
      (footprint "eagle-import:LED-TRICOLOR-5050-IC")
      (libsource (lib "eagle-import") (part "LED-TRICOLOR-5050-ICWS2811"))
    )
    (comp (ref "U8")
      (value "LED-TRICOLOR-5050-ICWS2811")
      (footprint "eagle-import:LED-TRICOLOR-5050-IC")
      (libsource (lib "eagle-import") (part "LED-TRICOLOR-5050-ICWS2811"))
    )
    (comp (ref "U9")
      (value "LED-TRICOLOR-5050-ICWS2811")
      (footprint "eagle-import:LED-TRICOLOR-5050-IC")
      (libsource (lib "eagle-import") (part "LED-TRICOLOR-5050-ICWS2811"))
    )
    (comp (ref "U10")
      (value "LED-TRICOLOR-5050-ICWS2811")
      (footprint "eagle-import:LED-TRICOLOR-5050-IC")
      (libsource (lib "eagle-import") (part "LED-TRICOLOR-5050-ICWS2811"))
    )
    (comp (ref "U11")
      (value "LED-TRICOLOR-5050-ICWS2811")
      (footprint "eagle-import:LED-TRICOLOR-5050-IC")
      (libsource (lib "eagle-import") (part "LED-TRICOLOR-5050-ICWS2811"))
    )
    (comp (ref "U12")
      (value "LED-TRICOLOR-5050-ICWS2811")
      (footprint "eagle-import:LED-TRICOLOR-5050-IC")
      (libsource (lib "eagle-import") (part "LED-TRICOLOR-5050-ICWS2811"))
    )
    (comp (ref "U13")
      (value "LED-TRICOLOR-5050-ICWS2811")
      (footprint "eagle-import:LED-TRICOLOR-5050-IC")
      (libsource (lib "eagle-import") (part "LED-TRICOLOR-5050-ICWS2811"))
    )
    (comp (ref "U14")
      (value "LED-TRICOLOR-5050-ICWS2811")
      (footprint "eagle-import:LED-TRICOLOR-5050-IC")
      (libsource (lib "eagle-import") (part "LED-TRICOLOR-5050-ICWS2811"))
    )
    (comp (ref "U15")
      (value "LED-TRICOLOR-5050-ICWS2811")
      (footprint "eagle-import:LED-TRICOLOR-5050-IC")
      (libsource (lib "eagle-import") (part "LED-TRICOLOR-5050-ICWS2811"))
    )
    (comp (ref "U16")
      (value "LED-TRICOLOR-5050-ICWS2811")
      (footprint "eagle-import:LED-TRICOLOR-5050-IC")
      (libsource (lib "eagle-import") (part "LED-TRICOLOR-5050-ICWS2811"))
    )
    (comp (ref "U17")
      (value "LED-TRICOLOR-5050-ICWS2811")
      (footprint "eagle-import:LED-TRICOLOR-5050-IC")
      (libsource (lib "eagle-import") (part "LED-TRICOLOR-5050-ICWS2811"))
    )
    (comp (ref "U18")
      (value "LED-TRICOLOR-5050-ICWS2811")
      (footprint "eagle-import:LED-TRICOLOR-5050-IC")
      (libsource (lib "eagle-import") (part "LED-TRICOLOR-5050-ICWS2811"))
    )
    (comp (ref "U19")
      (value "LED-TRICOLOR-5050-ICWS2811")
      (footprint "eagle-import:LED-TRICOLOR-5050-IC")
      (libsource (lib "eagle-import") (part "LED-TRICOLOR-5050-ICWS2811"))
    )
    (comp (ref "U20")
      (value "LED-TRICOLOR-5050-ICWS2811")
      (footprint "eagle-import:LED-TRICOLOR-5050-IC")
      (libsource (lib "eagle-import") (part "LED-TRICOLOR-5050-ICWS2811"))
    )
    (comp (ref "U21")
      (value "LED-TRICOLOR-5050-ICWS2811")
      (footprint "eagle-import:LED-TRICOLOR-5050-IC")
      (libsource (lib "eagle-import") (part "LED-TRICOLOR-5050-ICWS2811"))
    )
    (comp (ref "U22")
      (value "LED-TRICOLOR-5050-ICWS2811")
      (footprint "eagle-import:LED-TRICOLOR-5050-IC")
      (libsource (lib "eagle-import") (part "LED-TRICOLOR-5050-ICWS2811"))
    )
    (comp (ref "U23")
      (value "LED-TRICOLOR-5050-ICWS2811")
      (footprint "eagle-import:LED-TRICOLOR-5050-IC")
      (libsource (lib "eagle-import") (part "LED-TRICOLOR-5050-ICWS2811"))
    )
    (comp (ref "U24")
      (value "LED-TRICOLOR-5050-ICWS2811")
      (footprint "eagle-import:LED-TRICOLOR-5050-IC")
      (libsource (lib "eagle-import") (part "LED-TRICOLOR-5050-ICWS2811"))
    )
    (comp (ref "U25")
      (value "LED-TRICOLOR-5050-ICWS2811")
      (footprint "eagle-import:LED-TRICOLOR-5050-IC")
      (libsource (lib "eagle-import") (part "LED-TRICOLOR-5050-ICWS2811"))
    )
    (comp (ref "U26")
      (value "LED-TRICOLOR-5050-ICWS2811")
      (footprint "eagle-import:LED-TRICOLOR-5050-IC")
      (libsource (lib "eagle-import") (part "LED-TRICOLOR-5050-ICWS2811"))
    )
    (comp (ref "U27")
      (value "LED-TRICOLOR-5050-ICWS2811")
      (footprint "eagle-import:LED-TRICOLOR-5050-IC")
      (libsource (lib "eagle-import") (part "LED-TRICOLOR-5050-ICWS2811"))
    )
    (comp (ref "U28")
      (value "LED-TRICOLOR-5050-ICWS2811")
      (footprint "eagle-import:LED-TRICOLOR-5050-IC")
      (libsource (lib "eagle-import") (part "LED-TRICOLOR-5050-ICWS2811"))
    )
    (comp (ref "U29")
      (value "LED-TRICOLOR-5050-ICWS2811")
      (footprint "eagle-import:LED-TRICOLOR-5050-IC")
      (libsource (lib "eagle-import") (part "LED-TRICOLOR-5050-ICWS2811"))
    )
    (comp (ref "U30")
      (value "LED-TRICOLOR-5050-ICWS2811")
      (footprint "eagle-import:LED-TRICOLOR-5050-IC")
      (libsource (lib "eagle-import") (part "LED-TRICOLOR-5050-ICWS2811"))
    )
    (comp (ref "U31")
      (value "LED-TRICOLOR-5050-ICWS2811")
      (footprint "eagle-import:LED-TRICOLOR-5050-IC")
      (libsource (lib "eagle-import") (part "LED-TRICOLOR-5050-ICWS2811"))
    )
    (comp (ref "U32")
      (value "LED-TRICOLOR-5050-ICWS2811")
      (footprint "eagle-import:LED-TRICOLOR-5050-IC")
      (libsource (lib "eagle-import") (part "LED-TRICOLOR-5050-ICWS2811"))
    )
    (comp (ref "U33")
      (value "LED-TRICOLOR-5050-ICWS2811")
      (footprint "eagle-import:LED-TRICOLOR-5050-IC")
      (libsource (lib "eagle-import") (part "LED-TRICOLOR-5050-ICWS2811"))
    )
    (comp (ref "U34")
      (value "LED-TRICOLOR-5050-ICWS2811")
      (footprint "eagle-import:LED-TRICOLOR-5050-IC")
      (libsource (lib "eagle-import") (part "LED-TRICOLOR-5050-ICWS2811"))
    )
    (comp (ref "U35")
      (value "LED-TRICOLOR-5050-ICWS2811")
      (footprint "eagle-import:LED-TRICOLOR-5050-IC")
      (libsource (lib "eagle-import") (part "LED-TRICOLOR-5050-ICWS2811"))
    )
    (comp (ref "U36")
      (value "LED-TRICOLOR-5050-ICWS2811")
      (footprint "eagle-import:LED-TRICOLOR-5050-IC")
      (libsource (lib "eagle-import") (part "LED-TRICOLOR-5050-ICWS2811"))
    )
    (comp (ref "U37")
      (value "LED-TRICOLOR-5050-ICWS2811")
      (footprint "eagle-import:LED-TRICOLOR-5050-IC")
      (libsource (lib "eagle-import") (part "LED-TRICOLOR-5050-ICWS2811"))
    )
    (comp (ref "U38")
      (value "LED-TRICOLOR-5050-ICWS2811")
      (footprint "eagle-import:LED-TRICOLOR-5050-IC")
      (libsource (lib "eagle-import") (part "LED-TRICOLOR-5050-ICWS2811"))
    )
    (comp (ref "U39")
      (value "LED-TRICOLOR-5050-ICWS2811")
      (footprint "eagle-import:LED-TRICOLOR-5050-IC")
      (libsource (lib "eagle-import") (part "LED-TRICOLOR-5050-ICWS2811"))
    )
    (comp (ref "U40")
      (value "LED-TRICOLOR-5050-ICWS2811")
      (footprint "eagle-import:LED-TRICOLOR-5050-IC")
      (libsource (lib "eagle-import") (part "LED-TRICOLOR-5050-ICWS2811"))
    )
    (comp (ref "U41")
      (value "LED-TRICOLOR-5050-ICWS2811")
      (footprint "eagle-import:LED-TRICOLOR-5050-IC")
      (libsource (lib "eagle-import") (part "LED-TRICOLOR-5050-ICWS2811"))
    )
    (comp (ref "U42")
      (value "LED-TRICOLOR-5050-ICWS2811")
      (footprint "eagle-import:LED-TRICOLOR-5050-IC")
      (libsource (lib "eagle-import") (part "LED-TRICOLOR-5050-ICWS2811"))
    )
    (comp (ref "U43")
      (value "LED-TRICOLOR-5050-ICWS2811")
      (footprint "eagle-import:LED-TRICOLOR-5050-IC")
      (libsource (lib "eagle-import") (part "LED-TRICOLOR-5050-ICWS2811"))
    )
    (comp (ref "U44")
      (value "LED-TRICOLOR-5050-ICWS2811")
      (footprint "eagle-import:LED-TRICOLOR-5050-IC")
      (libsource (lib "eagle-import") (part "LED-TRICOLOR-5050-ICWS2811"))
    )
    (comp (ref "U45")
      (value "LED-TRICOLOR-5050-ICWS2811")
      (footprint "eagle-import:LED-TRICOLOR-5050-IC")
      (libsource (lib "eagle-import") (part "LED-TRICOLOR-5050-ICWS2811"))
    )
    (comp (ref "U46")
      (value "LED-TRICOLOR-5050-ICWS2811")
      (footprint "eagle-import:LED-TRICOLOR-5050-IC")
      (libsource (lib "eagle-import") (part "LED-TRICOLOR-5050-ICWS2811"))
    )
    (comp (ref "U47")
      (value "LED-TRICOLOR-5050-ICWS2811")
      (footprint "eagle-import:LED-TRICOLOR-5050-IC")
      (libsource (lib "eagle-import") (part "LED-TRICOLOR-5050-ICWS2811"))
    )
    (comp (ref "U48")
      (value "LED-TRICOLOR-5050-ICWS2811")
      (footprint "eagle-import:LED-TRICOLOR-5050-IC")
      (libsource (lib "eagle-import") (part "LED-TRICOLOR-5050-ICWS2811"))
    )
    (comp (ref "U49")
      (value "LED-TRICOLOR-5050-ICWS2811")
      (footprint "eagle-import:LED-TRICOLOR-5050-IC")
      (libsource (lib "eagle-import") (part "LED-TRICOLOR-5050-ICWS2811"))
    )
    (comp (ref "U50")
      (value "LED-TRICOLOR-5050-ICWS2811")
      (footprint "eagle-import:LED-TRICOLOR-5050-IC")
      (libsource (lib "eagle-import") (part "LED-TRICOLOR-5050-ICWS2811"))
    )
    (comp (ref "U51")
      (value "LED-TRICOLOR-5050-ICWS2811")
      (footprint "eagle-import:LED-TRICOLOR-5050-IC")
      (libsource (lib "eagle-import") (part "LED-TRICOLOR-5050-ICWS2811"))
    )
    (comp (ref "U52")
      (value "LED-TRICOLOR-5050-ICWS2811")
      (footprint "eagle-import:LED-TRICOLOR-5050-IC")
      (libsource (lib "eagle-import") (part "LED-TRICOLOR-5050-ICWS2811"))
    )
    (comp (ref "U53")
      (value "LED-TRICOLOR-5050-ICWS2811")
      (footprint "eagle-import:LED-TRICOLOR-5050-IC")
      (libsource (lib "eagle-import") (part "LED-TRICOLOR-5050-ICWS2811"))
    )
    (comp (ref "U54")
      (value "LED-TRICOLOR-5050-ICWS2811")
      (footprint "eagle-import:LED-TRICOLOR-5050-IC")
      (libsource (lib "eagle-import") (part "LED-TRICOLOR-5050-ICWS2811"))
    )
    (comp (ref "U55")
      (value "LED-TRICOLOR-5050-ICWS2811")
      (footprint "eagle-import:LED-TRICOLOR-5050-IC")
      (libsource (lib "eagle-import") (part "LED-TRICOLOR-5050-ICWS2811"))
    )
    (comp (ref "U58")
      (value "LED-TRICOLOR-5050-ICWS2811")
      (footprint "eagle-import:LED-TRICOLOR-5050-IC")
      (libsource (lib "eagle-import") (part "LED-TRICOLOR-5050-ICWS2811"))
    )
  )
  (nets
    (net (code "1") (name "+3V3") (class "Default")
      (node (ref "C11") (pin "1") (pinfunction "1_1") (pintype "passive"))
      (node (ref "C13") (pin "1") (pinfunction "1_1") (pintype "passive"))
      (node (ref "C14") (pin "1") (pinfunction "1_1") (pintype "passive"))
      (node (ref "C15") (pin "1") (pinfunction "1_1") (pintype "passive"))
      (node (ref "C16") (pin "1") (pinfunction "1_1") (pintype "passive"))
      (node (ref "C20") (pin "1") (pinfunction "1_1") (pintype "passive"))
      (node (ref "C59") (pin "1") (pinfunction "1_1") (pintype "passive"))
      (node (ref "C8") (pin "1") (pinfunction "1_1") (pintype "passive"))
      (node (ref "D2") (pin "1") (pinfunction "A1_1") (pintype "passive"))
      (node (ref "IC2") (pin "8") (pinfunction "V+_8") (pintype "power_in"))
      (node (ref "IC4") (pin "2") (pinfunction "OUT_2") (pintype "passive"))
      (node (ref "IC4") (pin "4") (pinfunction "OUT_4") (pintype "passive"))
      (node (ref "JP1") (pin "2") (pinfunction "2_2") (pintype "passive"))
      (node (ref "JP2") (pin "9") (pinfunction "9_9") (pintype "passive"))
      (node (ref "JP3") (pin "3") (pinfunction "3_3") (pintype "passive"))
      (node (ref "R10") (pin "1") (pinfunction "1_1") (pintype "passive"))
      (node (ref "R11") (pin "1") (pinfunction "1_1") (pintype "passive"))
      (node (ref "R12") (pin "2") (pinfunction "2_2") (pintype "passive"))
      (node (ref "R24") (pin "2") (pinfunction "2_2") (pintype "passive"))
      (node (ref "R25") (pin "2") (pinfunction "2_2") (pintype "passive"))
      (node (ref "R26") (pin "2") (pinfunction "2_2") (pintype "passive"))
      (node (ref "R29") (pin "1") (pinfunction "1_1") (pintype "passive"))
      (node (ref "R3") (pin "2") (pinfunction "2_2") (pintype "passive"))
      (node (ref "R30") (pin "2") (pinfunction "2_2") (pintype "passive"))
      (node (ref "R8") (pin "2") (pinfunction "P$2_2") (pintype "bidirectional"))
      (node (ref "U$5") (pin "13") (pinfunction "VDDA_13") (pintype "bidirectional"))
      (node (ref "U$5") (pin "14") (pinfunction "VREFH_14") (pintype "bidirectional"))
      (node (ref "U$5") (pin "3") (pinfunction "VDD_3") (pintype "bidirectional"))
      (node (ref "U$5") (pin "30") (pinfunction "VDD_30") (pintype "bidirectional"))
      (node (ref "U$5") (pin "48") (pinfunction "VDD_48") (pintype "bidirectional"))
      (node (ref "U$5") (pin "7") (pinfunction "VOUT33_7") (pintype "bidirectional"))
      (node (ref "U59") (pin "30") (pinfunction "VCHG_30") (pintype "bidirectional"))
      (node (ref "U59") (pin "31") (pinfunction "VBAT_SENSE_31") (pintype "bidirectional"))
      (node (ref "U59") (pin "32") (pinfunction "VBAT_32") (pintype "bidirectional"))
      (node (ref "U59") (pin "33") (pinfunction "VDD_PADS_33") (pintype "bidirectional"))
      (node (ref "U59") (pin "34") (pinfunction "3V3_USB_34") (pintype "bidirectional"))
    )
    (net (code "2") (name "+5V") (class "Default")
      (node (ref "C60") (pin "1") (pinfunction "1_1") (pintype "passive"))
      (node (ref "IC3") (pin "1") (pinfunction "OE_1") (pintype "input"))
      (node (ref "IC3") (pin "7") (pinfunction "OE_7") (pintype "input"))
      (node (ref "IC3") (pin "8") (pinfunction "VCC_8") (pintype "power_in"))
      (node (ref "IC4") (pin "3") (pinfunction "IN_3") (pintype "input"))
      (node (ref "OUT-CAP1") (pin "1") (pinfunction "1_1") (pintype "passive"))
      (node (ref "Q1") (pin "2") (pinfunction "E_2") (pintype "passive"))
      (node (ref "R16") (pin "1") (pinfunction "1_1") (pintype "passive"))
      (node (ref "R32") (pin "1") (pinfunction "1_1") (pintype "passive"))
      (node (ref "R40") (pin "1") (pinfunction "1_1") (pintype "passive"))
      (node (ref "SJ3") (pin "2") (pinfunction "2_2") (pintype "passive"))
      (node (ref "U$1") (pin "2") (pinfunction "2_2") (pintype "bidirectional"))
      (node (ref "U$6") (pin "P$10") (pinfunction "VCC-B_P$10") (pintype "power_in"))
      (node (ref "U$6") (pin "P$12") (pinfunction "VCC_P$12") (pintype "power_in"))
    )
    (net (code "3") (name "5VLED") (class "Default")
      (node (ref "C1") (pin "2") (pinfunction "2_2") (pintype "passive"))
      (node (ref "C17") (pin "2") (pinfunction "2_2") (pintype "passive"))
      (node (ref "C2") (pin "2") (pinfunction "2_2") (pintype "passive"))
      (node (ref "C22") (pin "2") (pinfunction "2_2") (pintype "passive"))
      (node (ref "C23") (pin "2") (pinfunction "2_2") (pintype "passive"))
      (node (ref "C24") (pin "2") (pinfunction "2_2") (pintype "passive"))
      (node (ref "C25") (pin "2") (pinfunction "2_2") (pintype "passive"))
      (node (ref "C26") (pin "2") (pinfunction "2_2") (pintype "passive"))
      (node (ref "C27") (pin "2") (pinfunction "2_2") (pintype "passive"))
      (node (ref "C28") (pin "2") (pinfunction "2_2") (pintype "passive"))
      (node (ref "C29") (pin "2") (pinfunction "2_2") (pintype "passive"))
      (node (ref "C3") (pin "2") (pinfunction "2_2") (pintype "passive"))
      (node (ref "C30") (pin "2") (pinfunction "2_2") (pintype "passive"))
      (node (ref "C31") (pin "2") (pinfunction "2_2") (pintype "passive"))
      (node (ref "C32") (pin "2") (pinfunction "2_2") (pintype "passive"))
      (node (ref "C33") (pin "2") (pinfunction "2_2") (pintype "passive"))
      (node (ref "C34") (pin "2") (pinfunction "2_2") (pintype "passive"))
      (node (ref "C35") (pin "2") (pinfunction "2_2") (pintype "passive"))
      (node (ref "C4") (pin "2") (pinfunction "2_2") (pintype "passive"))
      (node (ref "C44") (pin "2") (pinfunction "2_2") (pintype "passive"))
      (node (ref "C48") (pin "2") (pinfunction "2_2") (pintype "passive"))
      (node (ref "C49") (pin "2") (pinfunction "2_2") (pintype "passive"))
      (node (ref "C5") (pin "2") (pinfunction "2_2") (pintype "passive"))
      (node (ref "C50") (pin "2") (pinfunction "2_2") (pintype "passive"))
      (node (ref "C51") (pin "2") (pinfunction "2_2") (pintype "passive"))
      (node (ref "C52") (pin "2") (pinfunction "2_2") (pintype "passive"))
      (node (ref "C53") (pin "2") (pinfunction "2_2") (pintype "passive"))
      (node (ref "C54") (pin "2") (pinfunction "2_2") (pintype "passive"))
      (node (ref "C55") (pin "2") (pinfunction "2_2") (pintype "passive"))
      (node (ref "C56") (pin "2") (pinfunction "2_2") (pintype "passive"))
      (node (ref "C57") (pin "2") (pinfunction "2_2") (pintype "passive"))
      (node (ref "C58") (pin "2") (pinfunction "2_2") (pintype "passive"))
      (node (ref "C64") (pin "2") (pinfunction "2_2") (pintype "passive"))
      (node (ref "C65") (pin "2") (pinfunction "2_2") (pintype "passive"))
      (node (ref "C66") (pin "2") (pinfunction "2_2") (pintype "passive"))
      (node (ref "C67") (pin "2") (pinfunction "2_2") (pintype "passive"))
      (node (ref "C68") (pin "2") (pinfunction "2_2") (pintype "passive"))
      (node (ref "C69") (pin "2") (pinfunction "2_2") (pintype "passive"))
      (node (ref "C70") (pin "2") (pinfunction "2_2") (pintype "passive"))
      (node (ref "C71") (pin "2") (pinfunction "2_2") (pintype "passive"))
      (node (ref "C72") (pin "2") (pinfunction "2_2") (pintype "passive"))
      (node (ref "C73") (pin "2") (pinfunction "2_2") (pintype "passive"))
      (node (ref "C78") (pin "2") (pinfunction "2_2") (pintype "passive"))
      (node (ref "C79") (pin "2") (pinfunction "2_2") (pintype "passive"))
      (node (ref "C80") (pin "2") (pinfunction "2_2") (pintype "passive"))
      (node (ref "C85") (pin "2") (pinfunction "2_2") (pintype "passive"))
      (node (ref "C86") (pin "2") (pinfunction "2_2") (pintype "passive"))
      (node (ref "C87") (pin "2") (pinfunction "2_2") (pintype "passive"))
      (node (ref "C88") (pin "2") (pinfunction "2_2") (pintype "passive"))
      (node (ref "C89") (pin "2") (pinfunction "2_2") (pintype "passive"))
      (node (ref "C90") (pin "2") (pinfunction "2_2") (pintype "passive"))
      (node (ref "C91") (pin "2") (pinfunction "2_2") (pintype "passive"))
      (node (ref "C92") (pin "2") (pinfunction "2_2") (pintype "passive"))
      (node (ref "C93") (pin "2") (pinfunction "2_2") (pintype "passive"))
      (node (ref "C95") (pin "2") (pinfunction "2_2") (pintype "passive"))
      (node (ref "C98") (pin "2") (pinfunction "2_2") (pintype "passive"))
      (node (ref "JP6") (pin "1") (pinfunction "1_1") (pintype "passive"))
      (node (ref "OUT-CAP2") (pin "1") (pinfunction "1_1") (pintype "passive"))
      (node (ref "R20") (pin "1") (pinfunction "1_1") (pintype "passive"))
      (node (ref "U$2") (pin "2") (pinfunction "2_2") (pintype "bidirectional"))
      (node (ref "U1") (pin "1") (pinfunction "VDD_1") (pintype "bidirectional"))
      (node (ref "U10") (pin "1") (pinfunction "VDD_1") (pintype "bidirectional"))
      (node (ref "U11") (pin "1") (pinfunction "VDD_1") (pintype "bidirectional"))
      (node (ref "U12") (pin "1") (pinfunction "VDD_1") (pintype "bidirectional"))
      (node (ref "U13") (pin "1") (pinfunction "VDD_1") (pintype "bidirectional"))
      (node (ref "U14") (pin "1") (pinfunction "VDD_1") (pintype "bidirectional"))
      (node (ref "U15") (pin "1") (pinfunction "VDD_1") (pintype "bidirectional"))
      (node (ref "U16") (pin "1") (pinfunction "VDD_1") (pintype "bidirectional"))
      (node (ref "U17") (pin "1") (pinfunction "VDD_1") (pintype "bidirectional"))
      (node (ref "U18") (pin "1") (pinfunction "VDD_1") (pintype "bidirectional"))
      (node (ref "U19") (pin "1") (pinfunction "VDD_1") (pintype "bidirectional"))
      (node (ref "U2") (pin "1") (pinfunction "VDD_1") (pintype "bidirectional"))
      (node (ref "U20") (pin "1") (pinfunction "VDD_1") (pintype "bidirectional"))
      (node (ref "U21") (pin "1") (pinfunction "VDD_1") (pintype "bidirectional"))
      (node (ref "U22") (pin "1") (pinfunction "VDD_1") (pintype "bidirectional"))
      (node (ref "U23") (pin "1") (pinfunction "VDD_1") (pintype "bidirectional"))
      (node (ref "U24") (pin "1") (pinfunction "VDD_1") (pintype "bidirectional"))
      (node (ref "U25") (pin "1") (pinfunction "VDD_1") (pintype "bidirectional"))
      (node (ref "U26") (pin "1") (pinfunction "VDD_1") (pintype "bidirectional"))
      (node (ref "U27") (pin "1") (pinfunction "VDD_1") (pintype "bidirectional"))
      (node (ref "U28") (pin "1") (pinfunction "VDD_1") (pintype "bidirectional"))
      (node (ref "U29") (pin "1") (pinfunction "VDD_1") (pintype "bidirectional"))
      (node (ref "U3") (pin "1") (pinfunction "VDD_1") (pintype "bidirectional"))
      (node (ref "U30") (pin "1") (pinfunction "VDD_1") (pintype "bidirectional"))
      (node (ref "U31") (pin "1") (pinfunction "VDD_1") (pintype "bidirectional"))
      (node (ref "U32") (pin "1") (pinfunction "VDD_1") (pintype "bidirectional"))
      (node (ref "U33") (pin "1") (pinfunction "VDD_1") (pintype "bidirectional"))
      (node (ref "U34") (pin "1") (pinfunction "VDD_1") (pintype "bidirectional"))
      (node (ref "U35") (pin "1") (pinfunction "VDD_1") (pintype "bidirectional"))
      (node (ref "U36") (pin "1") (pinfunction "VDD_1") (pintype "bidirectional"))
      (node (ref "U37") (pin "1") (pinfunction "VDD_1") (pintype "bidirectional"))
      (node (ref "U38") (pin "1") (pinfunction "VDD_1") (pintype "bidirectional"))
      (node (ref "U39") (pin "1") (pinfunction "VDD_1") (pintype "bidirectional"))
      (node (ref "U4") (pin "1") (pinfunction "VDD_1") (pintype "bidirectional"))
      (node (ref "U40") (pin "1") (pinfunction "VDD_1") (pintype "bidirectional"))
      (node (ref "U41") (pin "1") (pinfunction "VDD_1") (pintype "bidirectional"))
      (node (ref "U42") (pin "1") (pinfunction "VDD_1") (pintype "bidirectional"))
      (node (ref "U43") (pin "1") (pinfunction "VDD_1") (pintype "bidirectional"))
      (node (ref "U44") (pin "1") (pinfunction "VDD_1") (pintype "bidirectional"))
      (node (ref "U45") (pin "1") (pinfunction "VDD_1") (pintype "bidirectional"))
      (node (ref "U46") (pin "1") (pinfunction "VDD_1") (pintype "bidirectional"))
      (node (ref "U47") (pin "1") (pinfunction "VDD_1") (pintype "bidirectional"))
      (node (ref "U48") (pin "1") (pinfunction "VDD_1") (pintype "bidirectional"))
      (node (ref "U49") (pin "1") (pinfunction "VDD_1") (pintype "bidirectional"))
      (node (ref "U5") (pin "1") (pinfunction "VDD_1") (pintype "bidirectional"))
      (node (ref "U50") (pin "1") (pinfunction "VDD_1") (pintype "bidirectional"))
      (node (ref "U51") (pin "1") (pinfunction "VDD_1") (pintype "bidirectional"))
      (node (ref "U52") (pin "1") (pinfunction "VDD_1") (pintype "bidirectional"))
      (node (ref "U53") (pin "1") (pinfunction "VDD_1") (pintype "bidirectional"))
      (node (ref "U54") (pin "1") (pinfunction "VDD_1") (pintype "bidirectional"))
      (node (ref "U55") (pin "1") (pinfunction "VDD_1") (pintype "bidirectional"))
      (node (ref "U58") (pin "1") (pinfunction "VDD_1") (pintype "bidirectional"))
      (node (ref "U6") (pin "1") (pinfunction "VDD_1") (pintype "bidirectional"))
      (node (ref "U7") (pin "1") (pinfunction "VDD_1") (pintype "bidirectional"))
      (node (ref "U8") (pin "1") (pinfunction "VDD_1") (pintype "bidirectional"))
      (node (ref "U9") (pin "1") (pinfunction "VDD_1") (pintype "bidirectional"))
    )
    (net (code "4") (name "A10") (class "Default")
      (node (ref "JP5") (pin "3") (pinfunction "3_3") (pintype "passive"))
      (node (ref "U$5") (pin "9") (pinfunction "ADC0_DP0_9") (pintype "bidirectional"))
    )
    (net (code "5") (name "A11") (class "Default")
      (node (ref "JP5") (pin "4") (pinfunction "4_4") (pintype "passive"))
      (node (ref "U$5") (pin "10") (pinfunction "ADC0_DM0_10") (pintype "bidirectional"))
    )
    (net (code "6") (name "AMPEN") (class "Default")
      (node (ref "IC3") (pin "3") (pinfunction "O_3") (pintype "tri_state"))
      (node (ref "R13") (pin "1") (pinfunction "1_1") (pintype "passive"))
      (node (ref "U$3") (pin "15") (pinfunction "SHDN_15") (pintype "bidirectional"))
    )
    (net (code "7") (name "BC0") (class "Default")
      (node (ref "R21") (pin "2") (pinfunction "2_2") (pintype "passive"))
      (node (ref "U$5") (pin "54") (pinfunction "PTC9_54") (pintype "bidirectional"))
      (node (ref "U59") (pin "23") (pinfunction "PIO_0_23") (pintype "bidirectional"))
    )
    (net (code "8") (name "BC1") (class "Default")
      (node (ref "U$5") (pin "53") (pinfunction "PTC8_53") (pintype "bidirectional"))
      (node (ref "U59") (pin "24") (pinfunction "PIO_1_24") (pintype "bidirectional"))
    )
    (net (code "9") (name "BC2") (class "Default")
      (node (ref "U$5") (pin "55") (pinfunction "PTC10_55") (pintype "bidirectional"))
      (node (ref "U59") (pin "50") (pinfunction "PIO_2_50") (pintype "bidirectional"))
    )
    (net (code "10") (name "BC4") (class "Default")
      (node (ref "U$5") (pin "56") (pinfunction "PTC11_56") (pintype "bidirectional"))
      (node (ref "U59") (pin "26") (pinfunction "PIO_4_26") (pintype "bidirectional"))
    )
    (net (code "11") (name "BC5") (class "Default")
      (node (ref "U$5") (pin "1") (pinfunction "PTE0_1") (pintype "bidirectional"))
      (node (ref "U59") (pin "25") (pinfunction "PIO_5_25") (pintype "bidirectional"))
    )
    (net (code "12") (name "COIL") (class "Default")
      (node (ref "JP8") (pin "2") (pinfunction "2_2") (pintype "passive"))
      (node (ref "U$5") (pin "11") (pinfunction "ADC0_DP3_11") (pintype "bidirectional"))
    )
    (net (code "13") (name "CS2") (class "Default")
      (node (ref "JP2") (pin "7") (pinfunction "7_7") (pintype "passive"))
      (node (ref "U$5") (pin "62") (pinfunction "PTD5_62") (pintype "bidirectional"))
    )
    (net (code "14") (name "CS3") (class "Default")
      (node (ref "JP4") (pin "4") (pinfunction "4_4") (pintype "passive"))
      (node (ref "U$5") (pin "63") (pinfunction "PTD6_63") (pintype "bidirectional"))
    )
    (net (code "15") (name "D3{slash}PWM") (class "Default")
      (node (ref "JP5") (pin "1") (pinfunction "1_1") (pintype "passive"))
      (node (ref "U$5") (pin "28") (pinfunction "PTA12_28") (pintype "bidirectional"))
    )
    (net (code "16") (name "D32{slash}TOUCH") (class "Default")
      (node (ref "JP5") (pin "2") (pinfunction "2_2") (pintype "passive"))
      (node (ref "U$5") (pin "41") (pinfunction "PTB18_41") (pintype "bidirectional"))
    )
    (net (code "17") (name "FBTN") (class "Default")
      (node (ref "S3") (pin "3") (pinfunction "2_3") (pintype "passive"))
      (node (ref "U$5") (pin "2") (pinfunction "PTE1_2") (pintype "bidirectional"))
    )
    (net (code "18") (name "GND") (class "Default")
      (node (ref "AOZ1015AI") (pin "1") (pinfunction "PGND_1") (pintype "bidirectional"))
      (node (ref "AOZ1015AI") (pin "3") (pinfunction "AGND_3") (pintype "bidirectional"))
      (node (ref "AOZ1015AI1") (pin "1") (pinfunction "PGND_1") (pintype "bidirectional"))
      (node (ref "AOZ1015AI1") (pin "3") (pinfunction "AGND_3") (pintype "bidirectional"))
      (node (ref "C1") (pin "1") (pinfunction "1_1") (pintype "passive"))
      (node (ref "C10") (pin "2") (pinfunction "2_2") (pintype "passive"))
      (node (ref "C11") (pin "2") (pinfunction "2_2") (pintype "passive"))
      (node (ref "C12") (pin "2") (pinfunction "2_2") (pintype "passive"))
      (node (ref "C13") (pin "2") (pinfunction "2_2") (pintype "passive"))
      (node (ref "C14") (pin "2") (pinfunction "2_2") (pintype "passive"))
      (node (ref "C15") (pin "2") (pinfunction "2_2") (pintype "passive"))
      (node (ref "C16") (pin "2") (pinfunction "2_2") (pintype "passive"))
      (node (ref "C17") (pin "1") (pinfunction "1_1") (pintype "passive"))
      (node (ref "C18") (pin "2") (pinfunction "2_2") (pintype "passive"))
      (node (ref "C19") (pin "2") (pinfunction "2_2") (pintype "passive"))
      (node (ref "C2") (pin "1") (pinfunction "1_1") (pintype "passive"))
      (node (ref "C20") (pin "2") (pinfunction "2_2") (pintype "passive"))
      (node (ref "C21") (pin "2") (pinfunction "2_2") (pintype "passive"))
      (node (ref "C22") (pin "1") (pinfunction "1_1") (pintype "passive"))
      (node (ref "C23") (pin "1") (pinfunction "1_1") (pintype "passive"))
      (node (ref "C24") (pin "1") (pinfunction "1_1") (pintype "passive"))
      (node (ref "C25") (pin "1") (pinfunction "1_1") (pintype "passive"))
      (node (ref "C26") (pin "1") (pinfunction "1_1") (pintype "passive"))
      (node (ref "C27") (pin "1") (pinfunction "1_1") (pintype "passive"))
      (node (ref "C28") (pin "1") (pinfunction "1_1") (pintype "passive"))
      (node (ref "C29") (pin "1") (pinfunction "1_1") (pintype "passive"))
      (node (ref "C3") (pin "1") (pinfunction "1_1") (pintype "passive"))
      (node (ref "C30") (pin "1") (pinfunction "1_1") (pintype "passive"))
      (node (ref "C31") (pin "1") (pinfunction "1_1") (pintype "passive"))
      (node (ref "C32") (pin "1") (pinfunction "1_1") (pintype "passive"))
      (node (ref "C33") (pin "1") (pinfunction "1_1") (pintype "passive"))
      (node (ref "C34") (pin "1") (pinfunction "1_1") (pintype "passive"))
      (node (ref "C35") (pin "1") (pinfunction "1_1") (pintype "passive"))
      (node (ref "C36") (pin "2") (pinfunction "2_2") (pintype "passive"))
      (node (ref "C37") (pin "2") (pinfunction "2_2") (pintype "passive"))
      (node (ref "C38") (pin "2") (pinfunction "2_2") (pintype "passive"))
      (node (ref "C39") (pin "1") (pinfunction "1_1") (pintype "passive"))
      (node (ref "C4") (pin "1") (pinfunction "1_1") (pintype "passive"))
      (node (ref "C44") (pin "1") (pinfunction "1_1") (pintype "passive"))
      (node (ref "C46") (pin "1") (pinfunction "1_1") (pintype "passive"))
      (node (ref "C48") (pin "1") (pinfunction "1_1") (pintype "passive"))
      (node (ref "C49") (pin "1") (pinfunction "1_1") (pintype "passive"))
      (node (ref "C5") (pin "1") (pinfunction "1_1") (pintype "passive"))
      (node (ref "C50") (pin "1") (pinfunction "1_1") (pintype "passive"))
      (node (ref "C51") (pin "1") (pinfunction "1_1") (pintype "passive"))
      (node (ref "C52") (pin "1") (pinfunction "1_1") (pintype "passive"))
      (node (ref "C53") (pin "1") (pinfunction "1_1") (pintype "passive"))
      (node (ref "C54") (pin "1") (pinfunction "1_1") (pintype "passive"))
      (node (ref "C55") (pin "1") (pinfunction "1_1") (pintype "passive"))
      (node (ref "C56") (pin "1") (pinfunction "1_1") (pintype "passive"))
      (node (ref "C57") (pin "1") (pinfunction "1_1") (pintype "passive"))
      (node (ref "C58") (pin "1") (pinfunction "1_1") (pintype "passive"))
      (node (ref "C59") (pin "2") (pinfunction "2_2") (pintype "passive"))
      (node (ref "C6") (pin "2") (pinfunction "2_2") (pintype "passive"))
      (node (ref "C60") (pin "2") (pinfunction "2_2") (pintype "passive"))
      (node (ref "C64") (pin "1") (pinfunction "1_1") (pintype "passive"))
      (node (ref "C65") (pin "1") (pinfunction "1_1") (pintype "passive"))
      (node (ref "C66") (pin "1") (pinfunction "1_1") (pintype "passive"))
      (node (ref "C67") (pin "1") (pinfunction "1_1") (pintype "passive"))
      (node (ref "C68") (pin "1") (pinfunction "1_1") (pintype "passive"))
      (node (ref "C69") (pin "1") (pinfunction "1_1") (pintype "passive"))
      (node (ref "C7") (pin "2") (pinfunction "2_2") (pintype "passive"))
      (node (ref "C70") (pin "1") (pinfunction "1_1") (pintype "passive"))
      (node (ref "C71") (pin "1") (pinfunction "1_1") (pintype "passive"))
      (node (ref "C72") (pin "1") (pinfunction "1_1") (pintype "passive"))
      (node (ref "C73") (pin "1") (pinfunction "1_1") (pintype "passive"))
      (node (ref "C78") (pin "1") (pinfunction "1_1") (pintype "passive"))
      (node (ref "C79") (pin "1") (pinfunction "1_1") (pintype "passive"))
      (node (ref "C8") (pin "2") (pinfunction "2_2") (pintype "passive"))
      (node (ref "C80") (pin "1") (pinfunction "1_1") (pintype "passive"))
      (node (ref "C85") (pin "1") (pinfunction "1_1") (pintype "passive"))
      (node (ref "C86") (pin "1") (pinfunction "1_1") (pintype "passive"))
      (node (ref "C87") (pin "1") (pinfunction "1_1") (pintype "passive"))
      (node (ref "C88") (pin "1") (pinfunction "1_1") (pintype "passive"))
      (node (ref "C89") (pin "1") (pinfunction "1_1") (pintype "passive"))
      (node (ref "C9") (pin "2") (pinfunction "2_2") (pintype "passive"))
      (node (ref "C90") (pin "1") (pinfunction "1_1") (pintype "passive"))
      (node (ref "C91") (pin "1") (pinfunction "1_1") (pintype "passive"))
      (node (ref "C92") (pin "1") (pinfunction "1_1") (pintype "passive"))
      (node (ref "C93") (pin "1") (pinfunction "1_1") (pintype "passive"))
      (node (ref "C95") (pin "1") (pinfunction "1_1") (pintype "passive"))
      (node (ref "C98") (pin "1") (pinfunction "1_1") (pintype "passive"))
      (node (ref "IC2") (pin "4") (pinfunction "V-_4") (pintype "power_in"))
      (node (ref "IC3") (pin "4") (pinfunction "GND_4") (pintype "power_in"))
      (node (ref "IC4") (pin "1") (pinfunction "GND/ADJ_1") (pintype "input"))
      (node (ref "IN-CAP") (pin "2") (pinfunction "2_2") (pintype "passive"))
      (node (ref "IN-CAP1") (pin "2") (pinfunction "2_2") (pintype "passive"))
      (node (ref "J1") (pin "GND") (pinfunction "GND_GND") (pintype "bidirectional"))
      (node (ref "J1") (pin "GNDBREAK") (pinfunction "GNDBREAK_GNDBREAK") (pintype "bidirectional"))
      (node (ref "J2") (pin "3") (pinfunction "VSS(GND)_3") (pintype "power_in"))
      (node (ref "JP1") (pin "1") (pinfunction "1_1") (pintype "passive"))
      (node (ref "JP2") (pin "8") (pinfunction "8_8") (pintype "passive"))
      (node (ref "JP3") (pin "4") (pinfunction "4_4") (pintype "passive"))
      (node (ref "JP6") (pin "3") (pinfunction "3_3") (pintype "passive"))
      (node (ref "JP8") (pin "1") (pinfunction "1_1") (pintype "passive"))
      (node (ref "OUT-CAP1") (pin "2") (pinfunction "2_2") (pintype "passive"))
      (node (ref "OUT-CAP2") (pin "2") (pinfunction "2_2") (pintype "passive"))
      (node (ref "Q2") (pin "2") (pinfunction "G2_2") (pintype "power_in"))
      (node (ref "Q2") (pin "4") (pinfunction "G1_4") (pintype "power_in"))
      (node (ref "Q3") (pin "2") (pinfunction "E_2") (pintype "passive"))
      (node (ref "R13") (pin "2") (pinfunction "2_2") (pintype "passive"))
      (node (ref "R17") (pin "2") (pinfunction "2_2") (pintype "passive"))
      (node (ref "R21") (pin "1") (pinfunction "1_1") (pintype "passive"))
      (node (ref "R22") (pin "1") (pinfunction "1_1") (pintype "passive"))
      (node (ref "R27") (pin "1") (pinfunction "1_1") (pintype "passive"))
      (node (ref "R28") (pin "2") (pinfunction "2_2") (pintype "passive"))
      (node (ref "R33") (pin "2") (pinfunction "2_2") (pintype "passive"))
      (node (ref "R37") (pin "1") (pinfunction "1_1") (pintype "passive"))
      (node (ref "R4") (pin "2") (pinfunction "2_2") (pintype "passive"))
      (node (ref "R42") (pin "2") (pinfunction "2_2") (pintype "passive"))
      (node (ref "R9") (pin "1") (pinfunction "1_1") (pintype "passive"))
      (node (ref "S1") (pin "1") (pinfunction "1_1") (pintype "passive"))
      (node (ref "S3") (pin "1") (pinfunction "1_1") (pintype "passive"))
      (node (ref "S4") (pin "1") (pinfunction "1_1") (pintype "passive"))
      (node (ref "SW1") (pin "1") (pinfunction "1_1") (pintype "passive"))
      (node (ref "SW1") (pin "2") (pinfunction "2_2") (pintype "passive"))
      (node (ref "U$3") (pin "10") (pinfunction "GND_10") (pintype "bidirectional"))
      (node (ref "U$3") (pin "19") (pinfunction "PGND_19") (pintype "bidirectional"))
      (node (ref "U$3") (pin "20") (pinfunction "PGND_20") (pintype "bidirectional"))
      (node (ref "U$3") (pin "23") (pinfunction "PGND_23") (pintype "bidirectional"))
      (node (ref "U$3") (pin "24") (pinfunction "PGND_24") (pintype "bidirectional"))
      (node (ref "U$3") (pin "5") (pinfunction "G1_5") (pintype "bidirectional"))
      (node (ref "U$3") (pin "7") (pinfunction "LIM_TH_7") (pintype "bidirectional"))
      (node (ref "U$3") (pin "EXP") (pinfunction "EP_EXP") (pintype "bidirectional"))
      (node (ref "U$4") (pin "2") (pinfunction "2_2") (pintype "passive"))
      (node (ref "U$5") (pin "15") (pinfunction "VREFL_15") (pintype "bidirectional"))
      (node (ref "U$5") (pin "16") (pinfunction "VSSA_16") (pintype "bidirectional"))
      (node (ref "U$5") (pin "31") (pinfunction "VSS_31") (pintype "bidirectional"))
      (node (ref "U$5") (pin "4") (pinfunction "VSS_4") (pintype "bidirectional"))
      (node (ref "U$5") (pin "47") (pinfunction "VSS_47") (pintype "bidirectional"))
      (node (ref "U$6") (pin "GND") (pinfunction "MOUNTS-GND_GND") (pintype "power_in"))
      (node (ref "U$6") (pin "P$11") (pinfunction "GND_P$11") (pintype "power_in"))
      (node (ref "U$6") (pin "P$2") (pinfunction "MOUNTS-GND_P$2") (pintype "power_in"))
      (node (ref "U$6") (pin "P$3") (pinfunction "MOUNTS-GND_P$3") (pintype "power_in"))
      (node (ref "U$6") (pin "P$4") (pinfunction "MOUNTS-GND_P$4") (pintype "power_in"))
      (node (ref "U$6") (pin "P$9") (pinfunction "GND-B_P$9") (pintype "power_in"))
      (node (ref "U$7") (pin "-") (pinfunction "-_-") (pintype "passive"))
      (node (ref "U$8") (pin "1") (pinfunction "GND_1") (pintype "bidirectional"))
      (node (ref "U$8") (pin "4") (pinfunction "GND2_4") (pintype "bidirectional"))
      (node (ref "U$8") (pin "5") (pinfunction "GND1_5") (pintype "bidirectional"))
      (node (ref "U1") (pin "3") (pinfunction "VSS_3") (pintype "bidirectional"))
      (node (ref "U10") (pin "3") (pinfunction "VSS_3") (pintype "bidirectional"))
      (node (ref "U11") (pin "3") (pinfunction "VSS_3") (pintype "bidirectional"))
      (node (ref "U12") (pin "3") (pinfunction "VSS_3") (pintype "bidirectional"))
      (node (ref "U13") (pin "3") (pinfunction "VSS_3") (pintype "bidirectional"))
      (node (ref "U14") (pin "3") (pinfunction "VSS_3") (pintype "bidirectional"))
      (node (ref "U15") (pin "3") (pinfunction "VSS_3") (pintype "bidirectional"))
      (node (ref "U16") (pin "3") (pinfunction "VSS_3") (pintype "bidirectional"))
      (node (ref "U17") (pin "3") (pinfunction "VSS_3") (pintype "bidirectional"))
      (node (ref "U18") (pin "3") (pinfunction "VSS_3") (pintype "bidirectional"))
      (node (ref "U19") (pin "3") (pinfunction "VSS_3") (pintype "bidirectional"))
      (node (ref "U2") (pin "3") (pinfunction "VSS_3") (pintype "bidirectional"))
      (node (ref "U20") (pin "3") (pinfunction "VSS_3") (pintype "bidirectional"))
      (node (ref "U21") (pin "3") (pinfunction "VSS_3") (pintype "bidirectional"))
      (node (ref "U22") (pin "3") (pinfunction "VSS_3") (pintype "bidirectional"))
      (node (ref "U23") (pin "3") (pinfunction "VSS_3") (pintype "bidirectional"))
      (node (ref "U24") (pin "3") (pinfunction "VSS_3") (pintype "bidirectional"))
      (node (ref "U25") (pin "3") (pinfunction "VSS_3") (pintype "bidirectional"))
      (node (ref "U26") (pin "3") (pinfunction "VSS_3") (pintype "bidirectional"))
      (node (ref "U27") (pin "3") (pinfunction "VSS_3") (pintype "bidirectional"))
      (node (ref "U28") (pin "3") (pinfunction "VSS_3") (pintype "bidirectional"))
      (node (ref "U29") (pin "3") (pinfunction "VSS_3") (pintype "bidirectional"))
      (node (ref "U3") (pin "3") (pinfunction "VSS_3") (pintype "bidirectional"))
      (node (ref "U30") (pin "3") (pinfunction "VSS_3") (pintype "bidirectional"))
      (node (ref "U31") (pin "3") (pinfunction "VSS_3") (pintype "bidirectional"))
      (node (ref "U32") (pin "3") (pinfunction "VSS_3") (pintype "bidirectional"))
      (node (ref "U33") (pin "3") (pinfunction "VSS_3") (pintype "bidirectional"))
      (node (ref "U34") (pin "3") (pinfunction "VSS_3") (pintype "bidirectional"))
      (node (ref "U35") (pin "3") (pinfunction "VSS_3") (pintype "bidirectional"))
      (node (ref "U36") (pin "3") (pinfunction "VSS_3") (pintype "bidirectional"))
      (node (ref "U37") (pin "3") (pinfunction "VSS_3") (pintype "bidirectional"))
      (node (ref "U38") (pin "3") (pinfunction "VSS_3") (pintype "bidirectional"))
      (node (ref "U39") (pin "3") (pinfunction "VSS_3") (pintype "bidirectional"))
      (node (ref "U4") (pin "3") (pinfunction "VSS_3") (pintype "bidirectional"))
      (node (ref "U40") (pin "3") (pinfunction "VSS_3") (pintype "bidirectional"))
      (node (ref "U41") (pin "3") (pinfunction "VSS_3") (pintype "bidirectional"))
      (node (ref "U42") (pin "3") (pinfunction "VSS_3") (pintype "bidirectional"))
      (node (ref "U43") (pin "3") (pinfunction "VSS_3") (pintype "bidirectional"))
      (node (ref "U44") (pin "3") (pinfunction "VSS_3") (pintype "bidirectional"))
      (node (ref "U45") (pin "3") (pinfunction "VSS_3") (pintype "bidirectional"))
      (node (ref "U46") (pin "3") (pinfunction "VSS_3") (pintype "bidirectional"))
      (node (ref "U47") (pin "3") (pinfunction "VSS_3") (pintype "bidirectional"))
      (node (ref "U48") (pin "3") (pinfunction "VSS_3") (pintype "bidirectional"))
      (node (ref "U49") (pin "3") (pinfunction "VSS_3") (pintype "bidirectional"))
      (node (ref "U5") (pin "3") (pinfunction "VSS_3") (pintype "bidirectional"))
      (node (ref "U50") (pin "3") (pinfunction "VSS_3") (pintype "bidirectional"))
      (node (ref "U51") (pin "3") (pinfunction "VSS_3") (pintype "bidirectional"))
      (node (ref "U52") (pin "3") (pinfunction "VSS_3") (pintype "bidirectional"))
      (node (ref "U53") (pin "3") (pinfunction "VSS_3") (pintype "bidirectional"))
      (node (ref "U54") (pin "3") (pinfunction "VSS_3") (pintype "bidirectional"))
      (node (ref "U55") (pin "3") (pinfunction "VSS_3") (pintype "bidirectional"))
      (node (ref "U58") (pin "3") (pinfunction "VSS_3") (pintype "bidirectional"))
      (node (ref "U59") (pin "1") (pinfunction "GND_1") (pintype "bidirectional"))
      (node (ref "U59") (pin "11") (pinfunction "GND_11") (pintype "bidirectional"))
      (node (ref "U59") (pin "2") (pinfunction "GND_2") (pintype "bidirectional"))
      (node (ref "U59") (pin "22") (pinfunction "GND_22") (pintype "bidirectional"))
      (node (ref "U59") (pin "27") (pinfunction "GND_27") (pintype "bidirectional"))
      (node (ref "U59") (pin "3") (pinfunction "GND_3") (pintype "bidirectional"))
      (node (ref "U59") (pin "4") (pinfunction "GND_4") (pintype "bidirectional"))
      (node (ref "U6") (pin "3") (pinfunction "VSS_3") (pintype "bidirectional"))
      (node (ref "U7") (pin "3") (pinfunction "VSS_3") (pintype "bidirectional"))
      (node (ref "U8") (pin "3") (pinfunction "VSS_3") (pintype "bidirectional"))
      (node (ref "U9") (pin "3") (pinfunction "VSS_3") (pintype "bidirectional"))
      (node (ref "X3") (pin "GND") (pinfunction "GND_GND") (pintype "bidirectional"))
      (node (ref "X3") (pin "P1") (pinfunction "GND_P1") (pintype "bidirectional"))
      (node (ref "X3") (pin "P2") (pinfunction "GND_P2") (pintype "bidirectional"))
      (node (ref "X3") (pin "P3") (pinfunction "GND_P3") (pintype "bidirectional"))
      (node (ref "X3") (pin "P4") (pinfunction "GND_P4") (pintype "bidirectional"))
      (node (ref "X3") (pin "P5") (pinfunction "GND_P5") (pintype "bidirectional"))
      (node (ref "X3") (pin "P6") (pinfunction "GND_P6") (pintype "bidirectional"))
    )
    (net (code "19") (name "IR") (class "Default")
      (node (ref "U$5") (pin "29") (pinfunction "PTA13_29") (pintype "bidirectional"))
      (node (ref "U$8") (pin "3") (pinfunction "OUT_3") (pintype "bidirectional"))
    )
    (net (code "20") (name "LBTN") (class "Default")
      (node (ref "S4") (pin "3") (pinfunction "2_3") (pintype "passive"))
      (node (ref "U$5") (pin "27") (pinfunction "PTA5_27") (pintype "bidirectional"))
    )
    (net (code "21") (name "LCD_LED") (class "Default")
      (node (ref "R2") (pin "1") (pinfunction "1_1") (pintype "passive"))
      (node (ref "U$5") (pin "61") (pinfunction "PTD4_61") (pintype "bidirectional"))
    )
    (net (code "22") (name "LCD_RESET") (class "Default")
      (node (ref "JP2") (pin "6") (pinfunction "6_6") (pintype "passive"))
      (node (ref "U$5") (pin "64") (pinfunction "PTD7_64") (pintype "bidirectional"))
    )
    (net (code "23") (name "LED") (class "Default")
      (node (ref "IC3") (pin "6") (pinfunction "O_6") (pintype "tri_state"))
      (node (ref "U45") (pin "4") (pinfunction "DI_4") (pintype "bidirectional"))
    )
    (net (code "24") (name "L_AUDIO") (class "Default")
      (node (ref "C45") (pin "2") (pinfunction "2_2") (pintype "passive"))
      (node (ref "R24") (pin "1") (pinfunction "1_1") (pintype "passive"))
      (node (ref "R27") (pin "2") (pinfunction "2_2") (pintype "passive"))
      (node (ref "U$5") (pin "36") (pinfunction "PTB1_36") (pintype "bidirectional"))
    )
    (net (code "25") (name "L_AUDIO_PRE") (class "Default")
      (node (ref "C45") (pin "1") (pinfunction "1_1") (pintype "passive"))
      (node (ref "IC2") (pin "1") (pinfunction "OUT_1") (pintype "output"))
      (node (ref "R7") (pin "1") (pinfunction "1_1") (pintype "passive"))
    )
    (net (code "26") (name "MIC_BIAS") (class "Default")
      (node (ref "SJ4") (pin "2") (pinfunction "2_2") (pintype "passive"))
      (node (ref "U59") (pin "17") (pinfunction "MIC_BIAS_A_17") (pintype "bidirectional"))
    )
    (net (code "27") (name "MIC_L+") (class "Default")
      (node (ref "R31") (pin "2") (pinfunction "2_2") (pintype "passive"))
      (node (ref "SJ4") (pin "1") (pinfunction "1_1") (pintype "passive"))
      (node (ref "U59") (pin "21") (pinfunction "MIC_LP_21") (pintype "bidirectional"))
    )
    (net (code "28") (name "MIC_L-") (class "Default")
      (node (ref "C46") (pin "2") (pinfunction "2_2") (pintype "passive"))
      (node (ref "L6") (pin "1") (pinfunction "1_1") (pintype "passive"))
      (node (ref "R31") (pin "1") (pinfunction "1_1") (pintype "passive"))
      (node (ref "U59") (pin "20") (pinfunction "MIC_LN_20") (pintype "bidirectional"))
    )
    (net (code "29") (name "MIC_R+") (class "Default")
      (node (ref "U59") (pin "19") (pinfunction "MIC_RP_19") (pintype "bidirectional"))
    )
    (net (code "30") (name "MIC_R-") (class "Default")
      (node (ref "U59") (pin "18") (pinfunction "MIC_RN_18") (pintype "bidirectional"))
    )
    (net (code "31") (name "MISO") (class "Default")
      (node (ref "JP2") (pin "1") (pinfunction "1_1") (pintype "passive"))
      (node (ref "JP4") (pin "2") (pinfunction "2_2") (pintype "passive"))
      (node (ref "U$5") (pin "52") (pinfunction "PTC7_52") (pintype "bidirectional"))
    )
    (net (code "32") (name "MOSI") (class "Default")
      (node (ref "JP2") (pin "4") (pinfunction "4_4") (pintype "passive"))
      (node (ref "JP4") (pin "3") (pinfunction "3_3") (pintype "passive"))
      (node (ref "U$5") (pin "51") (pinfunction "PTC6_51") (pintype "bidirectional"))
    )
    (net (code "33") (name "N$62") (class "Default")
      (node (ref "JP2") (pin "2") (pinfunction "2_2") (pintype "passive"))
      (node (ref "R38") (pin "2") (pinfunction "2_2") (pintype "passive"))
    )
    (net (code "34") (name "Net-(AOZ1015AI-COMP)") (class "Default")
      (node (ref "AOZ1015AI") (pin "5") (pinfunction "COMP_5") (pintype "bidirectional"))
      (node (ref "R15") (pin "1") (pinfunction "1_1") (pintype "passive"))
    )
    (net (code "35") (name "Net-(AOZ1015AI-EN)") (class "Default")
      (node (ref "AOZ1015AI") (pin "6") (pinfunction "EN_6") (pintype "bidirectional"))
      (node (ref "R14") (pin "1") (pinfunction "1_1") (pintype "passive"))
    )
    (net (code "36") (name "Net-(AOZ1015AI-FB)") (class "Default")
      (node (ref "AOZ1015AI") (pin "4") (pinfunction "FB_4") (pintype "bidirectional"))
      (node (ref "R16") (pin "2") (pinfunction "2_2") (pintype "passive"))
      (node (ref "R17") (pin "1") (pinfunction "1_1") (pintype "passive"))
    )
    (net (code "37") (name "Net-(AOZ1015AI-LX-Pad7)") (class "Default")
      (node (ref "AOZ1015AI") (pin "7") (pinfunction "LX_7") (pintype "bidirectional"))
      (node (ref "AOZ1015AI") (pin "8") (pinfunction "LX_8") (pintype "bidirectional"))
      (node (ref "U$1") (pin "1") (pinfunction "1_1") (pintype "bidirectional"))
    )
    (net (code "38") (name "Net-(AOZ1015AI1-COMP)") (class "Default")
      (node (ref "AOZ1015AI1") (pin "5") (pinfunction "COMP_5") (pintype "bidirectional"))
      (node (ref "R19") (pin "1") (pinfunction "1_1") (pintype "passive"))
    )
    (net (code "39") (name "Net-(AOZ1015AI1-EN)") (class "Default")
      (node (ref "AOZ1015AI1") (pin "6") (pinfunction "EN_6") (pintype "bidirectional"))
      (node (ref "R18") (pin "1") (pinfunction "1_1") (pintype "passive"))
    )
    (net (code "40") (name "Net-(AOZ1015AI1-FB)") (class "Default")
      (node (ref "AOZ1015AI1") (pin "4") (pinfunction "FB_4") (pintype "bidirectional"))
      (node (ref "R20") (pin "2") (pinfunction "2_2") (pintype "passive"))
      (node (ref "R28") (pin "1") (pinfunction "1_1") (pintype "passive"))
    )
    (net (code "41") (name "Net-(AOZ1015AI1-LX-Pad7)") (class "Default")
      (node (ref "AOZ1015AI1") (pin "7") (pinfunction "LX_7") (pintype "bidirectional"))
      (node (ref "AOZ1015AI1") (pin "8") (pinfunction "LX_8") (pintype "bidirectional"))
      (node (ref "U$2") (pin "1") (pinfunction "1_1") (pintype "bidirectional"))
    )
    (net (code "42") (name "Net-(C9-Pad1)") (class "Default")
      (node (ref "C9") (pin "1") (pinfunction "1_1") (pintype "passive"))
      (node (ref "R19") (pin "2") (pinfunction "2_2") (pintype "passive"))
    )
    (net (code "43") (name "Net-(C12-Pad1)") (class "Default")
      (node (ref "C12") (pin "1") (pinfunction "1_1") (pintype "passive"))
      (node (ref "R15") (pin "2") (pinfunction "2_2") (pintype "passive"))
    )
    (net (code "44") (name "Net-(CN1-1)") (class "Default")
      (node (ref "CN1") (pin "2") (pinfunction "1_2") (pintype "passive"))
      (node (ref "U$3") (pin "1") (pinfunction "OUTL-_1") (pintype "bidirectional"))
      (node (ref "U$3") (pin "2") (pinfunction "OUTL-_2") (pintype "bidirectional"))
    )
    (net (code "45") (name "Net-(CN1-2)") (class "Default")
      (node (ref "CN1") (pin "1") (pinfunction "2_1") (pintype "passive"))
      (node (ref "U$3") (pin "3") (pinfunction "OUTL+_3") (pintype "bidirectional"))
    )
    (net (code "46") (name "Net-(CN2-1)") (class "Default")
      (node (ref "CN2") (pin "2") (pinfunction "1_2") (pintype "passive"))
      (node (ref "U$3") (pin "17") (pinfunction "OUTR-_17") (pintype "bidirectional"))
      (node (ref "U$3") (pin "18") (pinfunction "OUTR-_18") (pintype "bidirectional"))
    )
    (net (code "47") (name "Net-(CN2-2)") (class "Default")
      (node (ref "CN2") (pin "1") (pinfunction "2_1") (pintype "passive"))
      (node (ref "U$3") (pin "16") (pinfunction "OUTR+_16") (pintype "bidirectional"))
    )
    (net (code "48") (name "Net-(D2-A2)") (class "Default")
      (node (ref "D2") (pin "2") (pinfunction "A2_2") (pintype "passive"))
      (node (ref "U$7") (pin "+1") (pinfunction "+_+1") (pintype "passive"))
      (node (ref "U$7") (pin "+2") (pinfunction "+1_+2") (pintype "passive"))
    )
    (net (code "49") (name "Net-(D2-CC)") (class "Default")
      (node (ref "C18") (pin "1") (pinfunction "1_1") (pintype "passive"))
      (node (ref "D2") (pin "3") (pinfunction "CC_3") (pintype "passive"))
      (node (ref "U$5") (pin "21") (pinfunction "VBAT_21") (pintype "bidirectional"))
    )
    (net (code "50") (name "Net-(IC2A-+IN)") (class "Default")
      (node (ref "IC2") (pin "3") (pinfunction "+IN_3") (pintype "input"))
      (node (ref "R22") (pin "2") (pinfunction "2_2") (pintype "passive"))
      (node (ref "R23") (pin "1") (pinfunction "1_1") (pintype "passive"))
    )
    (net (code "51") (name "Net-(IC2A--IN)") (class "Default")
      (node (ref "IC2") (pin "2") (pinfunction "-IN_2") (pintype "input"))
      (node (ref "R6") (pin "2") (pinfunction "2_2") (pintype "passive"))
      (node (ref "R7") (pin "2") (pinfunction "2_2") (pintype "passive"))
    )
    (net (code "52") (name "Net-(IC2B-+IN)") (class "Default")
      (node (ref "IC2") (pin "5") (pinfunction "+IN_5") (pintype "input"))
      (node (ref "R1") (pin "2") (pinfunction "2_2") (pintype "passive"))
      (node (ref "R4") (pin "1") (pinfunction "1_1") (pintype "passive"))
    )
    (net (code "53") (name "Net-(IC2B--IN)") (class "Default")
      (node (ref "IC2") (pin "6") (pinfunction "-IN_6") (pintype "input"))
      (node (ref "R36") (pin "2") (pinfunction "2_2") (pintype "passive"))
      (node (ref "R5") (pin "1") (pinfunction "1_1") (pintype "passive"))
    )
    (net (code "54") (name "Net-(IC3A-I)") (class "Default")
      (node (ref "IC3") (pin "2") (pinfunction "I_2") (pintype "input"))
      (node (ref "U$5") (pin "45") (pinfunction "PTC2_45") (pintype "bidirectional"))
    )
    (net (code "55") (name "Net-(IC3B-I)") (class "Default")
      (node (ref "IC3") (pin "5") (pinfunction "I_5") (pintype "input"))
      (node (ref "U$5") (pin "44") (pinfunction "PTC1_44") (pintype "bidirectional"))
    )
    (net (code "56") (name "Net-(JP1-Pad7)") (class "Default")
      (node (ref "JP1") (pin "7") (pinfunction "7_7") (pintype "passive"))
      (node (ref "R11") (pin "2") (pinfunction "2_2") (pintype "passive"))
    )
    (net (code "57") (name "Net-(L6-Pad2)") (class "Default")
      (node (ref "L6") (pin "2") (pinfunction "2_2") (pintype "passive"))
      (node (ref "U$4") (pin "1") (pinfunction "1_1") (pintype "passive"))
    )
    (net (code "58") (name "Net-(Q1-B)") (class "Default")
      (node (ref "Q1") (pin "1") (pinfunction "B_1") (pintype "passive"))
      (node (ref "R39") (pin "1") (pinfunction "1_1") (pintype "passive"))
    )
    (net (code "59") (name "Net-(Q1-C)") (class "Default")
      (node (ref "Q1") (pin "3") (pinfunction "C_3") (pintype "passive"))
      (node (ref "R38") (pin "1") (pinfunction "1_1") (pintype "passive"))
      (node (ref "SJ3") (pin "1") (pinfunction "1_1") (pintype "passive"))
    )
    (net (code "60") (name "Net-(Q2-X1)") (class "Default")
      (node (ref "Q2") (pin "1") (pinfunction "X1_1") (pintype "bidirectional"))
      (node (ref "U$5") (pin "33") (pinfunction "PTA19_33") (pintype "bidirectional"))
    )
    (net (code "61") (name "Net-(Q2-X2)") (class "Default")
      (node (ref "Q2") (pin "3") (pinfunction "X2_3") (pintype "bidirectional"))
      (node (ref "U$5") (pin "32") (pinfunction "PTA18_32") (pintype "bidirectional"))
    )
    (net (code "62") (name "Net-(Q3-B)") (class "Default")
      (node (ref "Q3") (pin "1") (pinfunction "B_1") (pintype "passive"))
      (node (ref "R2") (pin "2") (pinfunction "2_2") (pintype "passive"))
    )
    (net (code "63") (name "Net-(Q3-C)") (class "Default")
      (node (ref "Q3") (pin "3") (pinfunction "C_3") (pintype "passive"))
      (node (ref "R39") (pin "2") (pinfunction "2_2") (pintype "passive"))
    )
    (net (code "64") (name "Net-(R8-P$1)") (class "Default")
      (node (ref "R8") (pin "1") (pinfunction "P$1_1") (pintype "bidirectional"))
      (node (ref "R9") (pin "2") (pinfunction "2_2") (pintype "passive"))
      (node (ref "U$5") (pin "12") (pinfunction "ADC0_DM3_12") (pintype "bidirectional"))
    )
    (net (code "65") (name "Net-(R34-Pad1)") (class "Default")
      (node (ref "R34") (pin "1") (pinfunction "1_1") (pintype "passive"))
      (node (ref "X3") (pin "D-") (pinfunction "D-_D-") (pintype "bidirectional"))
    )
    (net (code "66") (name "Net-(R35-Pad1)") (class "Default")
      (node (ref "R35") (pin "1") (pinfunction "1_1") (pintype "passive"))
      (node (ref "X3") (pin "D+") (pinfunction "D+_D+") (pintype "bidirectional"))
    )
    (net (code "67") (name "Net-(R41-Pad2)") (class "Default")
      (node (ref "R41") (pin "2") (pinfunction "2_2") (pintype "passive"))
      (node (ref "R42") (pin "1") (pinfunction "1_1") (pintype "passive"))
    )
    (net (code "68") (name "Net-(U$3-G2)") (class "Default")
      (node (ref "C36") (pin "1") (pinfunction "1_1") (pintype "passive"))
      (node (ref "U$3") (pin "4") (pinfunction "VS_4") (pintype "bidirectional"))
      (node (ref "U$3") (pin "6") (pinfunction "G2_6") (pintype "bidirectional"))
    )
    (net (code "69") (name "Net-(U$3-INL+)") (class "Default")
      (node (ref "C42") (pin "1") (pinfunction "1_1") (pintype "passive"))
      (node (ref "U$3") (pin "8") (pinfunction "INL+_8") (pintype "bidirectional"))
    )
    (net (code "70") (name "Net-(U$3-INL-)") (class "Default")
      (node (ref "C43") (pin "1") (pinfunction "1_1") (pintype "passive"))
      (node (ref "U$3") (pin "9") (pinfunction "INL-_9") (pintype "bidirectional"))
    )
    (net (code "71") (name "Net-(U$3-INR+)") (class "Default")
      (node (ref "C40") (pin "1") (pinfunction "1_1") (pintype "passive"))
      (node (ref "U$3") (pin "11") (pinfunction "INR+_11") (pintype "bidirectional"))
    )
    (net (code "72") (name "Net-(U$3-INR-)") (class "Default")
      (node (ref "C41") (pin "1") (pinfunction "1_1") (pintype "passive"))
      (node (ref "U$3") (pin "12") (pinfunction "INR-_12") (pintype "bidirectional"))
    )
    (net (code "73") (name "Net-(U$3-RELEASE)") (class "Default")
      (node (ref "C37") (pin "1") (pinfunction "1_1") (pintype "passive"))
      (node (ref "U$3") (pin "14") (pinfunction "RELEASE_14") (pintype "bidirectional"))
    )
    (net (code "74") (name "Net-(U$5-EXTAL32)") (class "Default")
      (node (ref "U$5") (pin "20") (pinfunction "EXTAL32_20") (pintype "bidirectional"))
      (node (ref "Y2") (pin "P$2") (pinfunction "2_P$2") (pintype "bidirectional"))
    )
    (net (code "75") (name "Net-(U$5-PTA4)") (class "Default")
      (node (ref "C6") (pin "1") (pinfunction "1_1") (pintype "passive"))
      (node (ref "R26") (pin "1") (pinfunction "1_1") (pintype "passive"))
      (node (ref "U$5") (pin "26") (pinfunction "PTA4_26") (pintype "bidirectional"))
    )
    (net (code "76") (name "Net-(U$5-PTB0)") (class "Default")
      (node (ref "U$5") (pin "35") (pinfunction "PTB0_35") (pintype "bidirectional"))
      (node (ref "U$5") (pin "43") (pinfunction "PTC0_43") (pintype "bidirectional"))
    )
    (net (code "77") (name "Net-(U$5-USB0_DM)") (class "Default")
      (node (ref "R34") (pin "2") (pinfunction "2_2") (pintype "passive"))
      (node (ref "U$5") (pin "6") (pinfunction "USB0_DM_6") (pintype "bidirectional"))
    )
    (net (code "78") (name "Net-(U$5-USB0_DP)") (class "Default")
      (node (ref "R35") (pin "2") (pinfunction "2_2") (pintype "passive"))
      (node (ref "U$5") (pin "5") (pinfunction "USB0_DP_5") (pintype "bidirectional"))
    )
    (net (code "79") (name "Net-(U$5-VREF_OUT)") (class "Default")
      (node (ref "C19") (pin "1") (pinfunction "1_1") (pintype "passive"))
      (node (ref "U$5") (pin "17") (pinfunction "VREF_OUT_17") (pintype "bidirectional"))
    )
    (net (code "80") (name "Net-(U$5-VREGIN)") (class "Default")
      (node (ref "C10") (pin "1") (pinfunction "1_1") (pintype "passive"))
      (node (ref "U$5") (pin "8") (pinfunction "VREGIN_8") (pintype "bidirectional"))
    )
    (net (code "81") (name "Net-(U$5-XTAL32)") (class "Default")
      (node (ref "U$5") (pin "19") (pinfunction "XTAL32_19") (pintype "bidirectional"))
      (node (ref "Y2") (pin "P$1") (pinfunction "1_P$1") (pintype "bidirectional"))
    )
    (net (code "82") (name "Net-(U$6-D+(B))") (class "Default")
      (node (ref "R32") (pin "2") (pinfunction "2_2") (pintype "passive"))
      (node (ref "R33") (pin "1") (pinfunction "1_1") (pintype "passive"))
      (node (ref "U$6") (pin "P$6") (pinfunction "D+(B)_P$6") (pintype "bidirectional"))
      (node (ref "U$6") (pin "P$8") (pinfunction "D+_P$8") (pintype "bidirectional"))
    )
    (net (code "83") (name "Net-(U$6-D-(B))") (class "Default")
      (node (ref "R40") (pin "2") (pinfunction "2_2") (pintype "passive"))
      (node (ref "R41") (pin "1") (pinfunction "1_1") (pintype "passive"))
      (node (ref "U$6") (pin "P$5") (pinfunction "D-(B)_P$5") (pintype "bidirectional"))
      (node (ref "U$6") (pin "P$7") (pinfunction "D-_P$7") (pintype "bidirectional"))
    )
    (net (code "84") (name "Net-(U$8-VS)") (class "Default")
      (node (ref "C7") (pin "1") (pinfunction "1_1") (pintype "passive"))
      (node (ref "R10") (pin "2") (pinfunction "2_2") (pintype "passive"))
      (node (ref "U$8") (pin "2") (pinfunction "VS_2") (pintype "bidirectional"))
    )
    (net (code "85") (name "Net-(U1-DI)") (class "Default")
      (node (ref "U1") (pin "4") (pinfunction "DI_4") (pintype "bidirectional"))
      (node (ref "U18") (pin "2") (pinfunction "DO_2") (pintype "bidirectional"))
    )
    (net (code "86") (name "Net-(U1-DO)") (class "Default")
      (node (ref "U1") (pin "2") (pinfunction "DO_2") (pintype "bidirectional"))
      (node (ref "U2") (pin "4") (pinfunction "DI_4") (pintype "bidirectional"))
    )
    (net (code "87") (name "Net-(U3-DI)") (class "Default")
      (node (ref "U3") (pin "4") (pinfunction "DI_4") (pintype "bidirectional"))
      (node (ref "U37") (pin "2") (pinfunction "DO_2") (pintype "bidirectional"))
    )
    (net (code "88") (name "Net-(U3-DO)") (class "Default")
      (node (ref "U3") (pin "2") (pinfunction "DO_2") (pintype "bidirectional"))
      (node (ref "U4") (pin "4") (pinfunction "DI_4") (pintype "bidirectional"))
    )
    (net (code "89") (name "Net-(U4-DO)") (class "Default")
      (node (ref "U4") (pin "2") (pinfunction "DO_2") (pintype "bidirectional"))
      (node (ref "U5") (pin "4") (pinfunction "DI_4") (pintype "bidirectional"))
    )
    (net (code "90") (name "Net-(U5-DO)") (class "Default")
      (node (ref "U5") (pin "2") (pinfunction "DO_2") (pintype "bidirectional"))
      (node (ref "U6") (pin "4") (pinfunction "DI_4") (pintype "bidirectional"))
    )
    (net (code "91") (name "Net-(U6-DO)") (class "Default")
      (node (ref "U6") (pin "2") (pinfunction "DO_2") (pintype "bidirectional"))
      (node (ref "U7") (pin "4") (pinfunction "DI_4") (pintype "bidirectional"))
    )
    (net (code "92") (name "Net-(U7-DO)") (class "Default")
      (node (ref "U7") (pin "2") (pinfunction "DO_2") (pintype "bidirectional"))
      (node (ref "U8") (pin "4") (pinfunction "DI_4") (pintype "bidirectional"))
    )
    (net (code "93") (name "Net-(U8-DO)") (class "Default")
      (node (ref "U8") (pin "2") (pinfunction "DO_2") (pintype "bidirectional"))
      (node (ref "U9") (pin "4") (pinfunction "DI_4") (pintype "bidirectional"))
    )
    (net (code "94") (name "Net-(U10-DI)") (class "Default")
      (node (ref "U10") (pin "4") (pinfunction "DI_4") (pintype "bidirectional"))
      (node (ref "U52") (pin "2") (pinfunction "DO_2") (pintype "bidirectional"))
    )
    (net (code "95") (name "Net-(U10-DO)") (class "Default")
      (node (ref "U10") (pin "2") (pinfunction "DO_2") (pintype "bidirectional"))
      (node (ref "U11") (pin "4") (pinfunction "DI_4") (pintype "bidirectional"))
    )
    (net (code "96") (name "Net-(U11-DO)") (class "Default")
      (node (ref "U11") (pin "2") (pinfunction "DO_2") (pintype "bidirectional"))
      (node (ref "U12") (pin "4") (pinfunction "DI_4") (pintype "bidirectional"))
    )
    (net (code "97") (name "Net-(U12-DO)") (class "Default")
      (node (ref "U12") (pin "2") (pinfunction "DO_2") (pintype "bidirectional"))
      (node (ref "U13") (pin "4") (pinfunction "DI_4") (pintype "bidirectional"))
    )
    (net (code "98") (name "Net-(U13-DO)") (class "Default")
      (node (ref "U13") (pin "2") (pinfunction "DO_2") (pintype "bidirectional"))
      (node (ref "U14") (pin "4") (pinfunction "DI_4") (pintype "bidirectional"))
    )
    (net (code "99") (name "Net-(U14-DO)") (class "Default")
      (node (ref "U14") (pin "2") (pinfunction "DO_2") (pintype "bidirectional"))
      (node (ref "U15") (pin "4") (pinfunction "DI_4") (pintype "bidirectional"))
    )
    (net (code "100") (name "Net-(U15-DO)") (class "Default")
      (node (ref "U15") (pin "2") (pinfunction "DO_2") (pintype "bidirectional"))
      (node (ref "U16") (pin "4") (pinfunction "DI_4") (pintype "bidirectional"))
    )
    (net (code "101") (name "Net-(U16-DO)") (class "Default")
      (node (ref "U16") (pin "2") (pinfunction "DO_2") (pintype "bidirectional"))
      (node (ref "U53") (pin "4") (pinfunction "DI_4") (pintype "bidirectional"))
    )
    (net (code "102") (name "Net-(U17-DI)") (class "Default")
      (node (ref "U17") (pin "4") (pinfunction "DI_4") (pintype "bidirectional"))
      (node (ref "U53") (pin "2") (pinfunction "DO_2") (pintype "bidirectional"))
    )
    (net (code "103") (name "Net-(U17-DO)") (class "Default")
      (node (ref "U17") (pin "2") (pinfunction "DO_2") (pintype "bidirectional"))
      (node (ref "U18") (pin "4") (pinfunction "DI_4") (pintype "bidirectional"))
    )
    (net (code "104") (name "Net-(U19-DI)") (class "Default")
      (node (ref "U19") (pin "4") (pinfunction "DI_4") (pintype "bidirectional"))
      (node (ref "U2") (pin "2") (pinfunction "DO_2") (pintype "bidirectional"))
    )
    (net (code "105") (name "Net-(U19-DO)") (class "Default")
      (node (ref "U19") (pin "2") (pinfunction "DO_2") (pintype "bidirectional"))
      (node (ref "U20") (pin "4") (pinfunction "DI_4") (pintype "bidirectional"))
    )
    (net (code "106") (name "Net-(U20-DO)") (class "Default")
      (node (ref "U20") (pin "2") (pinfunction "DO_2") (pintype "bidirectional"))
      (node (ref "U21") (pin "4") (pinfunction "DI_4") (pintype "bidirectional"))
    )
    (net (code "107") (name "Net-(U21-DO)") (class "Default")
      (node (ref "U21") (pin "2") (pinfunction "DO_2") (pintype "bidirectional"))
      (node (ref "U22") (pin "4") (pinfunction "DI_4") (pintype "bidirectional"))
    )
    (net (code "108") (name "Net-(U22-DO)") (class "Default")
      (node (ref "U22") (pin "2") (pinfunction "DO_2") (pintype "bidirectional"))
      (node (ref "U24") (pin "4") (pinfunction "DI_4") (pintype "bidirectional"))
    )
    (net (code "109") (name "Net-(U23-DI)") (class "Default")
      (node (ref "U23") (pin "4") (pinfunction "DI_4") (pintype "bidirectional"))
      (node (ref "U40") (pin "2") (pinfunction "DO_2") (pintype "bidirectional"))
    )
    (net (code "110") (name "Net-(U23-DO)") (class "Default")
      (node (ref "U23") (pin "2") (pinfunction "DO_2") (pintype "bidirectional"))
      (node (ref "U34") (pin "4") (pinfunction "DI_4") (pintype "bidirectional"))
    )
    (net (code "111") (name "Net-(U24-DO)") (class "Default")
      (node (ref "U24") (pin "2") (pinfunction "DO_2") (pintype "bidirectional"))
      (node (ref "U25") (pin "4") (pinfunction "DI_4") (pintype "bidirectional"))
    )
    (net (code "112") (name "Net-(U25-DO)") (class "Default")
      (node (ref "U25") (pin "2") (pinfunction "DO_2") (pintype "bidirectional"))
      (node (ref "U26") (pin "4") (pinfunction "DI_4") (pintype "bidirectional"))
    )
    (net (code "113") (name "Net-(U26-DO)") (class "Default")
      (node (ref "U26") (pin "2") (pinfunction "DO_2") (pintype "bidirectional"))
      (node (ref "U27") (pin "4") (pinfunction "DI_4") (pintype "bidirectional"))
    )
    (net (code "114") (name "Net-(U27-DO)") (class "Default")
      (node (ref "U27") (pin "2") (pinfunction "DO_2") (pintype "bidirectional"))
      (node (ref "U28") (pin "4") (pinfunction "DI_4") (pintype "bidirectional"))
    )
    (net (code "115") (name "Net-(U28-DO)") (class "Default")
      (node (ref "U28") (pin "2") (pinfunction "DO_2") (pintype "bidirectional"))
      (node (ref "U29") (pin "4") (pinfunction "DI_4") (pintype "bidirectional"))
    )
    (net (code "116") (name "Net-(U29-DO)") (class "Default")
      (node (ref "U29") (pin "2") (pinfunction "DO_2") (pintype "bidirectional"))
      (node (ref "U30") (pin "4") (pinfunction "DI_4") (pintype "bidirectional"))
    )
    (net (code "117") (name "Net-(U30-DO)") (class "Default")
      (node (ref "U30") (pin "2") (pinfunction "DO_2") (pintype "bidirectional"))
      (node (ref "U55") (pin "4") (pinfunction "DI_4") (pintype "bidirectional"))
    )
    (net (code "118") (name "Net-(U31-DI)") (class "Default")
      (node (ref "U31") (pin "4") (pinfunction "DI_4") (pintype "bidirectional"))
      (node (ref "U55") (pin "2") (pinfunction "DO_2") (pintype "bidirectional"))
    )
    (net (code "119") (name "Net-(U31-DO)") (class "Default")
      (node (ref "U31") (pin "2") (pinfunction "DO_2") (pintype "bidirectional"))
      (node (ref "U32") (pin "4") (pinfunction "DI_4") (pintype "bidirectional"))
    )
    (net (code "120") (name "Net-(U32-DO)") (class "Default")
      (node (ref "U32") (pin "2") (pinfunction "DO_2") (pintype "bidirectional"))
      (node (ref "U33") (pin "4") (pinfunction "DI_4") (pintype "bidirectional"))
    )
    (net (code "121") (name "Net-(U33-DO)") (class "Default")
      (node (ref "U33") (pin "2") (pinfunction "DO_2") (pintype "bidirectional"))
      (node (ref "U41") (pin "4") (pinfunction "DI_4") (pintype "bidirectional"))
    )
    (net (code "122") (name "Net-(U34-DO)") (class "Default")
      (node (ref "U34") (pin "2") (pinfunction "DO_2") (pintype "bidirectional"))
      (node (ref "U35") (pin "4") (pinfunction "DI_4") (pintype "bidirectional"))
    )
    (net (code "123") (name "Net-(U35-DO)") (class "Default")
      (node (ref "U35") (pin "2") (pinfunction "DO_2") (pintype "bidirectional"))
      (node (ref "U36") (pin "4") (pinfunction "DI_4") (pintype "bidirectional"))
    )
    (net (code "124") (name "Net-(U36-DO)") (class "Default")
      (node (ref "U36") (pin "2") (pinfunction "DO_2") (pintype "bidirectional"))
      (node (ref "U37") (pin "4") (pinfunction "DI_4") (pintype "bidirectional"))
    )
    (net (code "125") (name "Net-(U38-DI)") (class "Default")
      (node (ref "U38") (pin "4") (pinfunction "DI_4") (pintype "bidirectional"))
      (node (ref "U58") (pin "2") (pinfunction "DO_2") (pintype "bidirectional"))
    )
    (net (code "126") (name "Net-(U38-DO)") (class "Default")
      (node (ref "U38") (pin "2") (pinfunction "DO_2") (pintype "bidirectional"))
      (node (ref "U39") (pin "4") (pinfunction "DI_4") (pintype "bidirectional"))
    )
    (net (code "127") (name "Net-(U39-DO)") (class "Default")
      (node (ref "U39") (pin "2") (pinfunction "DO_2") (pintype "bidirectional"))
      (node (ref "U40") (pin "4") (pinfunction "DI_4") (pintype "bidirectional"))
    )
    (net (code "128") (name "Net-(U41-DO)") (class "Default")
      (node (ref "U41") (pin "2") (pinfunction "DO_2") (pintype "bidirectional"))
      (node (ref "U42") (pin "4") (pinfunction "DI_4") (pintype "bidirectional"))
    )
    (net (code "129") (name "Net-(U42-DO)") (class "Default")
      (node (ref "U42") (pin "2") (pinfunction "DO_2") (pintype "bidirectional"))
      (node (ref "U43") (pin "4") (pinfunction "DI_4") (pintype "bidirectional"))
    )
    (net (code "130") (name "Net-(U43-DO)") (class "Default")
      (node (ref "U43") (pin "2") (pinfunction "DO_2") (pintype "bidirectional"))
      (node (ref "U44") (pin "4") (pinfunction "DI_4") (pintype "bidirectional"))
    )
    (net (code "131") (name "Net-(U44-DO)") (class "Default")
      (node (ref "U44") (pin "2") (pinfunction "DO_2") (pintype "bidirectional"))
      (node (ref "U54") (pin "4") (pinfunction "DI_4") (pintype "bidirectional"))
    )
    (net (code "132") (name "Net-(U45-DO)") (class "Default")
      (node (ref "U45") (pin "2") (pinfunction "DO_2") (pintype "bidirectional"))
      (node (ref "U46") (pin "4") (pinfunction "DI_4") (pintype "bidirectional"))
    )
    (net (code "133") (name "Net-(U46-DO)") (class "Default")
      (node (ref "U46") (pin "2") (pinfunction "DO_2") (pintype "bidirectional"))
      (node (ref "U47") (pin "4") (pinfunction "DI_4") (pintype "bidirectional"))
    )
    (net (code "134") (name "Net-(U47-DO)") (class "Default")
      (node (ref "U47") (pin "2") (pinfunction "DO_2") (pintype "bidirectional"))
      (node (ref "U48") (pin "4") (pinfunction "DI_4") (pintype "bidirectional"))
    )
    (net (code "135") (name "Net-(U48-DO)") (class "Default")
      (node (ref "U48") (pin "2") (pinfunction "DO_2") (pintype "bidirectional"))
      (node (ref "U49") (pin "4") (pinfunction "DI_4") (pintype "bidirectional"))
    )
    (net (code "136") (name "Net-(U49-DO)") (class "Default")
      (node (ref "U49") (pin "2") (pinfunction "DO_2") (pintype "bidirectional"))
      (node (ref "U50") (pin "4") (pinfunction "DI_4") (pintype "bidirectional"))
    )
    (net (code "137") (name "Net-(U50-DO)") (class "Default")
      (node (ref "U50") (pin "2") (pinfunction "DO_2") (pintype "bidirectional"))
      (node (ref "U51") (pin "4") (pinfunction "DI_4") (pintype "bidirectional"))
    )
    (net (code "138") (name "Net-(U51-DO)") (class "Default")
      (node (ref "U51") (pin "2") (pinfunction "DO_2") (pintype "bidirectional"))
      (node (ref "U58") (pin "4") (pinfunction "DI_4") (pintype "bidirectional"))
    )
    (net (code "139") (name "Net-(U52-DI)") (class "Default")
      (node (ref "U52") (pin "4") (pinfunction "DI_4") (pintype "bidirectional"))
      (node (ref "U9") (pin "2") (pinfunction "DO_2") (pintype "bidirectional"))
    )
    (net (code "140") (name "Net-(U54-DO)") (class "Default")
      (node (ref "JP6") (pin "2") (pinfunction "2_2") (pintype "passive"))
      (node (ref "U54") (pin "2") (pinfunction "DO_2") (pintype "bidirectional"))
    )
    (net (code "141") (name "Net-(U59D-~{RESET})") (class "Default")
      (node (ref "R3") (pin "1") (pinfunction "1_1") (pintype "passive"))
      (node (ref "U59") (pin "44") (pinfunction "~{RESET}_44") (pintype "bidirectional"))
    )
    (net (code "142") (name "P2") (class "Default")
      (node (ref "JP2") (pin "5") (pinfunction "5_5") (pintype "passive"))
      (node (ref "U$5") (pin "57") (pinfunction "PTD0_57") (pintype "bidirectional"))
    )
    (net (code "143") (name "RBTN") (class "Default")
      (node (ref "S1") (pin "3") (pinfunction "2_3") (pintype "passive"))
      (node (ref "U$5") (pin "42") (pinfunction "PTB19_42") (pintype "bidirectional"))
    )
    (net (code "144") (name "RESET") (class "Default")
      (node (ref "C21") (pin "1") (pinfunction "1_1") (pintype "passive"))
      (node (ref "J2") (pin "5") (pinfunction "ICSP_CLK/PGC_5") (pintype "output"))
      (node (ref "R29") (pin "2") (pinfunction "2_2") (pintype "passive"))
      (node (ref "SW1") (pin "3") (pinfunction "3_3") (pintype "passive"))
      (node (ref "SW1") (pin "4") (pinfunction "4_4") (pintype "passive"))
      (node (ref "U$5") (pin "34") (pinfunction "RESET_B_34") (pintype "bidirectional"))
    )
    (net (code "145") (name "RX1") (class "Default")
      (node (ref "JP1") (pin "6") (pinfunction "6_6") (pintype "passive"))
      (node (ref "U$5") (pin "39") (pinfunction "PTB16_39") (pintype "bidirectional"))
    )
    (net (code "146") (name "RX2") (class "Default")
      (node (ref "U$5") (pin "46") (pinfunction "PTC3_46") (pintype "bidirectional"))
      (node (ref "U59") (pin "41") (pinfunction "UART_TX_41") (pintype "bidirectional"))
    )
    (net (code "147") (name "R_AUDIO") (class "Default")
      (node (ref "C47") (pin "2") (pinfunction "2_2") (pintype "passive"))
      (node (ref "R30") (pin "1") (pinfunction "1_1") (pintype "passive"))
      (node (ref "R37") (pin "2") (pinfunction "2_2") (pintype "passive"))
      (node (ref "U$5") (pin "58") (pinfunction "PTD1_58") (pintype "bidirectional"))
    )
    (net (code "148") (name "R_AUDIO_PRE") (class "Default")
      (node (ref "C47") (pin "1") (pinfunction "1_1") (pintype "passive"))
      (node (ref "IC2") (pin "7") (pinfunction "OUT_7") (pintype "output"))
      (node (ref "R5") (pin "2") (pinfunction "2_2") (pintype "passive"))
    )
    (net (code "149") (name "SCL") (class "Default")
      (node (ref "JP3") (pin "1") (pinfunction "1_1") (pintype "passive"))
      (node (ref "U$5") (pin "37") (pinfunction "PTB2_37") (pintype "bidirectional"))
    )
    (net (code "150") (name "SDA") (class "Default")
      (node (ref "JP3") (pin "2") (pinfunction "2_2") (pintype "passive"))
      (node (ref "U$5") (pin "38") (pinfunction "PTB3_38") (pintype "bidirectional"))
    )
    (net (code "151") (name "SPCK") (class "Default")
      (node (ref "JP2") (pin "3") (pinfunction "3_3") (pintype "passive"))
      (node (ref "JP4") (pin "1") (pinfunction "1_1") (pintype "passive"))
      (node (ref "U$5") (pin "50") (pinfunction "PTC5_50") (pintype "bidirectional"))
    )
    (net (code "152") (name "SPKR_L+") (class "Default")
      (node (ref "C42") (pin "2") (pinfunction "2_2") (pintype "passive"))
      (node (ref "R23") (pin "2") (pinfunction "2_2") (pintype "passive"))
      (node (ref "U59") (pin "14") (pinfunction "SPKR_LP_14") (pintype "bidirectional"))
    )
    (net (code "153") (name "SPKR_L-") (class "Default")
      (node (ref "C43") (pin "2") (pinfunction "2_2") (pintype "passive"))
      (node (ref "R6") (pin "1") (pinfunction "1_1") (pintype "passive"))
      (node (ref "U59") (pin "13") (pinfunction "SPKR_LN_13") (pintype "bidirectional"))
    )
    (net (code "154") (name "SPKR_R+") (class "Default")
      (node (ref "C40") (pin "2") (pinfunction "2_2") (pintype "passive"))
      (node (ref "R1") (pin "1") (pinfunction "1_1") (pintype "passive"))
      (node (ref "U59") (pin "16") (pinfunction "SPKR_RP_16") (pintype "bidirectional"))
    )
    (net (code "155") (name "SPKR_R-") (class "Default")
      (node (ref "C41") (pin "2") (pinfunction "2_2") (pintype "passive"))
      (node (ref "R36") (pin "1") (pinfunction "1_1") (pintype "passive"))
      (node (ref "U59") (pin "15") (pinfunction "SPKR_RN_15") (pintype "bidirectional"))
    )
    (net (code "156") (name "TCK") (class "Default")
      (node (ref "J2") (pin "1") (pinfunction "VPP/MCLR_1") (pintype "passive"))
      (node (ref "U$5") (pin "22") (pinfunction "PTA0_22") (pintype "bidirectional"))
    )
    (net (code "157") (name "TDI") (class "Default")
      (node (ref "J2") (pin "2") (pinfunction "VDD_2") (pintype "power_in"))
      (node (ref "U$5") (pin "23") (pinfunction "PTA1_23") (pintype "bidirectional"))
    )
    (net (code "158") (name "TDO") (class "Default")
      (node (ref "J2") (pin "4") (pinfunction "ICSP_DAT/PGD_4") (pintype "bidirectional"))
      (node (ref "U$5") (pin "24") (pinfunction "PTA2_24") (pintype "bidirectional"))
    )
    (net (code "159") (name "TMS") (class "Default")
      (node (ref "J2") (pin "6") (pinfunction "LVP_6") (pintype "bidirectional"))
      (node (ref "U$5") (pin "25") (pinfunction "PTA3_25") (pintype "bidirectional"))
    )
    (net (code "160") (name "TX1") (class "Default")
      (node (ref "JP1") (pin "5") (pinfunction "5_5") (pintype "passive"))
      (node (ref "U$5") (pin "40") (pinfunction "PTB17_40") (pintype "bidirectional"))
    )
    (net (code "161") (name "TX2") (class "Default")
      (node (ref "U$5") (pin "49") (pinfunction "PTC4_49") (pintype "bidirectional"))
      (node (ref "U59") (pin "42") (pinfunction "UART_RX_42") (pintype "bidirectional"))
    )
    (net (code "162") (name "VIN") (class "Default")
      (node (ref "AOZ1015AI") (pin "2") (pinfunction "VIN_2") (pintype "bidirectional"))
      (node (ref "AOZ1015AI1") (pin "2") (pinfunction "VIN_2") (pintype "bidirectional"))
      (node (ref "C38") (pin "1") (pinfunction "1_1") (pintype "passive"))
      (node (ref "C39") (pin "2") (pinfunction "2_2") (pintype "passive"))
      (node (ref "IN-CAP") (pin "1") (pinfunction "1_1") (pintype "passive"))
      (node (ref "IN-CAP1") (pin "1") (pinfunction "1_1") (pintype "passive"))
      (node (ref "J1") (pin "PWR") (pinfunction "PWR_PWR") (pintype "bidirectional"))
      (node (ref "JP8") (pin "3") (pinfunction "3_3") (pintype "passive"))
      (node (ref "R14") (pin "2") (pinfunction "2_2") (pintype "passive"))
      (node (ref "R18") (pin "2") (pinfunction "2_2") (pintype "passive"))
      (node (ref "U$3") (pin "21") (pinfunction "PVDD_21") (pintype "bidirectional"))
      (node (ref "U$3") (pin "22") (pinfunction "PVDD_22") (pintype "bidirectional"))
    )
    (net (code "163") (name "WIFI_RESTORE") (class "Default")
      (node (ref "JP1") (pin "3") (pinfunction "3_3") (pintype "passive"))
      (node (ref "R12") (pin "1") (pinfunction "1_1") (pintype "passive"))
      (node (ref "U$5") (pin "59") (pinfunction "PTD2_59") (pintype "bidirectional"))
    )
    (net (code "164") (name "WIFI_RST") (class "Default")
      (node (ref "JP1") (pin "4") (pinfunction "4_4") (pintype "passive"))
      (node (ref "R25") (pin "1") (pinfunction "1_1") (pintype "passive"))
      (node (ref "U$5") (pin "60") (pinfunction "PTD3_60") (pintype "bidirectional"))
    )
    (net (code "165") (name "unconnected-(JP1-Pad8)") (class "Default")
      (node (ref "JP1") (pin "8") (pinfunction "8_8") (pintype "passive"))
    )
    (net (code "166") (name "unconnected-(JP1-Pad9)") (class "Default")
      (node (ref "JP1") (pin "9") (pinfunction "9_9") (pintype "passive"))
    )
    (net (code "167") (name "unconnected-(JP1-Pad10)") (class "Default")
      (node (ref "JP1") (pin "10") (pinfunction "10_10") (pintype "passive"))
    )
    (net (code "168") (name "unconnected-(U$3-TEMPLOCK-Pad13)") (class "Default")
      (node (ref "U$3") (pin "13") (pinfunction "TEMPLOCK_13") (pintype "bidirectional"))
    )
    (net (code "169") (name "unconnected-(U59B-PCM_CLK{slash}CLK-Pad47)") (class "Default")
      (node (ref "U59") (pin "47") (pinfunction "PCM_CLK/CLK_47") (pintype "bidirectional"))
    )
    (net (code "170") (name "unconnected-(U59B-PCM_IN{slash}MOSI-Pad49)") (class "Default")
      (node (ref "U59") (pin "49") (pinfunction "PCM_IN/MOSI_49") (pintype "bidirectional"))
    )
    (net (code "171") (name "unconnected-(U59B-PCM_OUT{slash}MISO-Pad48)") (class "Default")
      (node (ref "U59") (pin "48") (pinfunction "PCM_OUT/MISO_48") (pintype "bidirectional"))
    )
    (net (code "172") (name "unconnected-(U59B-PCM_SYNC{slash}CSB-Pad46)") (class "Default")
      (node (ref "U59") (pin "46") (pinfunction "PCM_SYNC/CSB_46") (pintype "bidirectional"))
    )
    (net (code "173") (name "unconnected-(U59B-SPI_~{PCM}-Pad45)") (class "Default")
      (node (ref "U59") (pin "45") (pinfunction "SPI_~{PCM}_45") (pintype "bidirectional"))
    )
    (net (code "174") (name "unconnected-(U59B-UART_CTS-Pad40)") (class "Default")
      (node (ref "U59") (pin "40") (pinfunction "UART_CTS_40") (pintype "bidirectional"))
    )
    (net (code "175") (name "unconnected-(U59B-UART_RTS-Pad43)") (class "Default")
      (node (ref "U59") (pin "43") (pinfunction "UART_RTS_43") (pintype "bidirectional"))
    )
    (net (code "176") (name "unconnected-(U59B-USB_N-Pad35)") (class "Default")
      (node (ref "U59") (pin "35") (pinfunction "USB_N_35") (pintype "bidirectional"))
    )
    (net (code "177") (name "unconnected-(U59B-USB_P-Pad36)") (class "Default")
      (node (ref "U59") (pin "36") (pinfunction "USB_P_36") (pintype "bidirectional"))
    )
    (net (code "178") (name "unconnected-(U59C-AIO_1-Pad12)") (class "Default")
      (node (ref "U59") (pin "12") (pinfunction "AIO_1_12") (pintype "bidirectional"))
    )
    (net (code "179") (name "unconnected-(U59C-CAP_SENSE_1-Pad7)") (class "Default")
      (node (ref "U59") (pin "7") (pinfunction "CAP_SENSE_1_7") (pintype "bidirectional"))
    )
    (net (code "180") (name "unconnected-(U59C-CAP_SENSE_2-Pad10)") (class "Default")
      (node (ref "U59") (pin "10") (pinfunction "CAP_SENSE_2_10") (pintype "bidirectional"))
    )
    (net (code "181") (name "unconnected-(U59C-CAP_SENSE_3-Pad9)") (class "Default")
      (node (ref "U59") (pin "9") (pinfunction "CAP_SENSE_3_9") (pintype "bidirectional"))
    )
    (net (code "182") (name "unconnected-(U59C-CAP_SENSE_4-Pad8)") (class "Default")
      (node (ref "U59") (pin "8") (pinfunction "CAP_SENSE_4_8") (pintype "bidirectional"))
    )
    (net (code "183") (name "unconnected-(U59C-LED_0-Pad37)") (class "Default")
      (node (ref "U59") (pin "37") (pinfunction "LED_0_37") (pintype "bidirectional"))
    )
    (net (code "184") (name "unconnected-(U59C-LED_1-Pad38)") (class "Default")
      (node (ref "U59") (pin "38") (pinfunction "LED_1_38") (pintype "bidirectional"))
    )
    (net (code "185") (name "unconnected-(U59C-LED_2-Pad39)") (class "Default")
      (node (ref "U59") (pin "39") (pinfunction "LED_2_39") (pintype "bidirectional"))
    )
    (net (code "186") (name "unconnected-(U59C-PIO_3-Pad51)") (class "Default")
      (node (ref "U59") (pin "51") (pinfunction "PIO_3_51") (pintype "bidirectional"))
    )
    (net (code "187") (name "unconnected-(U59C-PIO_6-Pad5)") (class "Default")
      (node (ref "U59") (pin "5") (pinfunction "PIO_6_5") (pintype "bidirectional"))
    )
    (net (code "188") (name "unconnected-(U59C-PIO_7-Pad6)") (class "Default")
      (node (ref "U59") (pin "6") (pinfunction "PIO_7_6") (pintype "bidirectional"))
    )
    (net (code "189") (name "unconnected-(U59D-CHG_EXT-Pad29)") (class "Default")
      (node (ref "U59") (pin "29") (pinfunction "CHG_EXT_29") (pintype "bidirectional"))
    )
    (net (code "190") (name "unconnected-(U59D-VREGEN-Pad28)") (class "Default")
      (node (ref "U59") (pin "28") (pinfunction "VREGEN_28") (pintype "bidirectional"))
    )
    (net (code "191") (name "unconnected-(X3-PadVBUS)") (class "Default")
      (node (ref "X3") (pin "VBUS") (pinfunction "VBUS_VBUS") (pintype "bidirectional"))
    )
  )
)
